# LinTempCont_4ch_V1_1.net
KiCad netlist of a schematic drawn in EAGLE
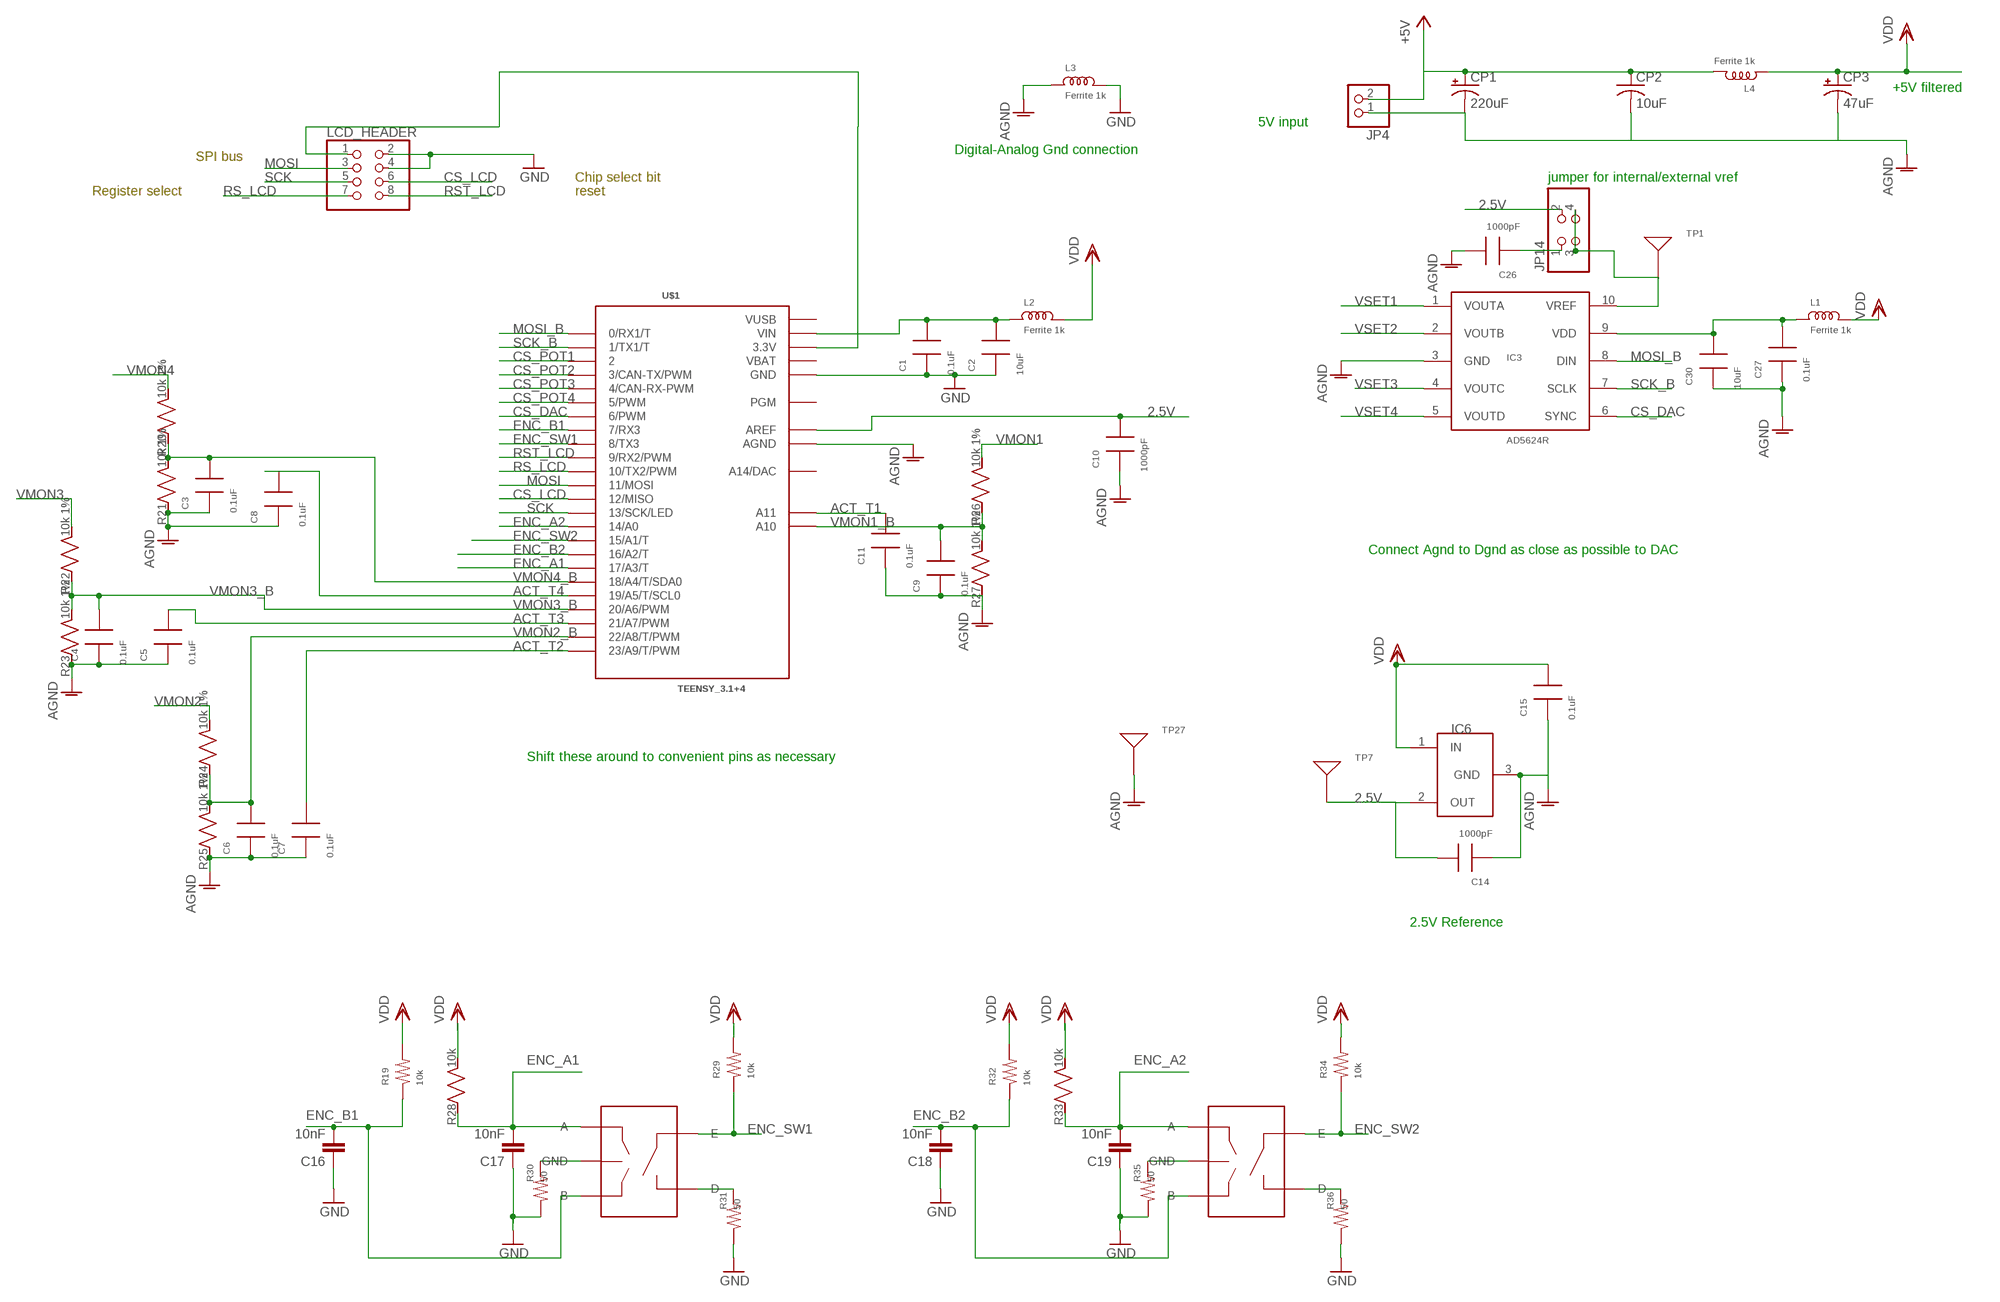
[diagram p0: schematic, sheet 1]
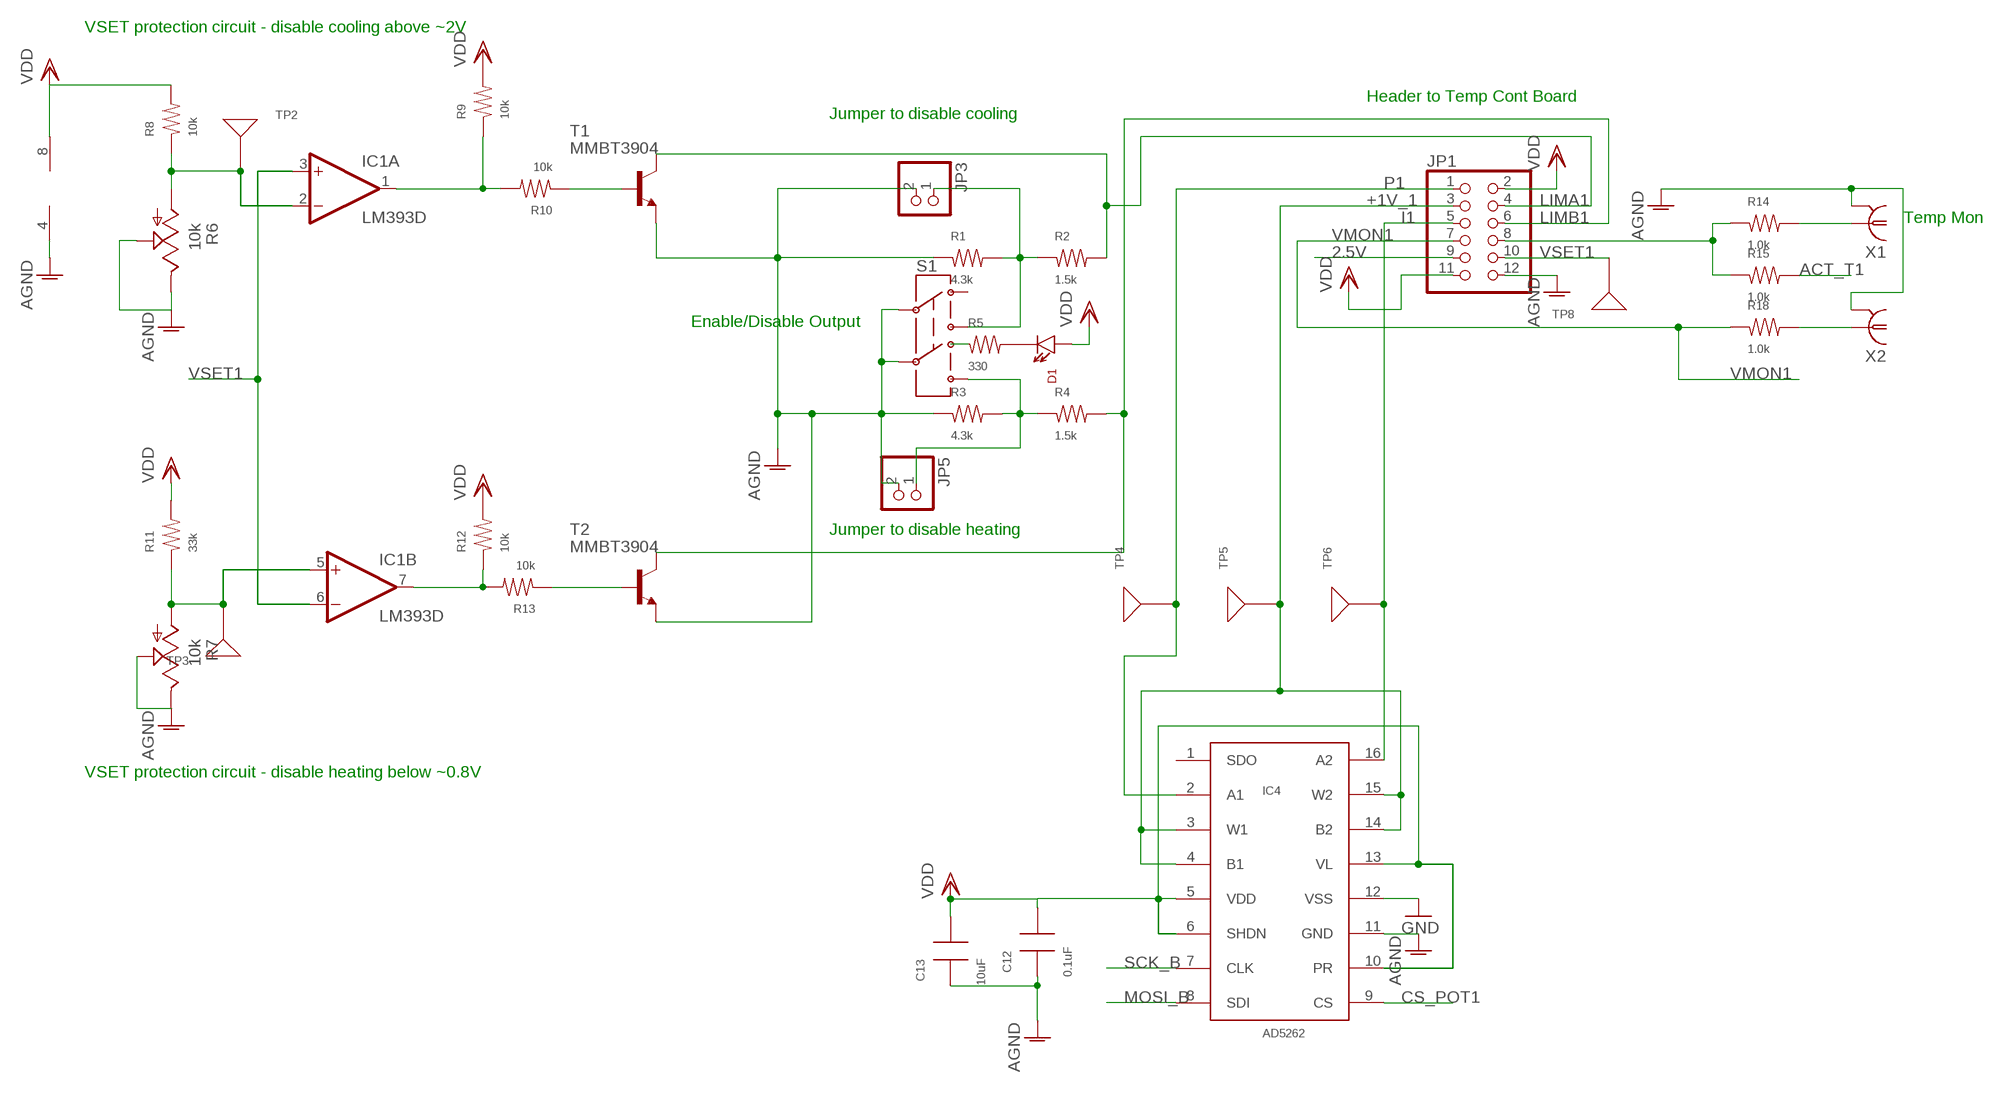
[diagram p1: schematic, sheet 2]
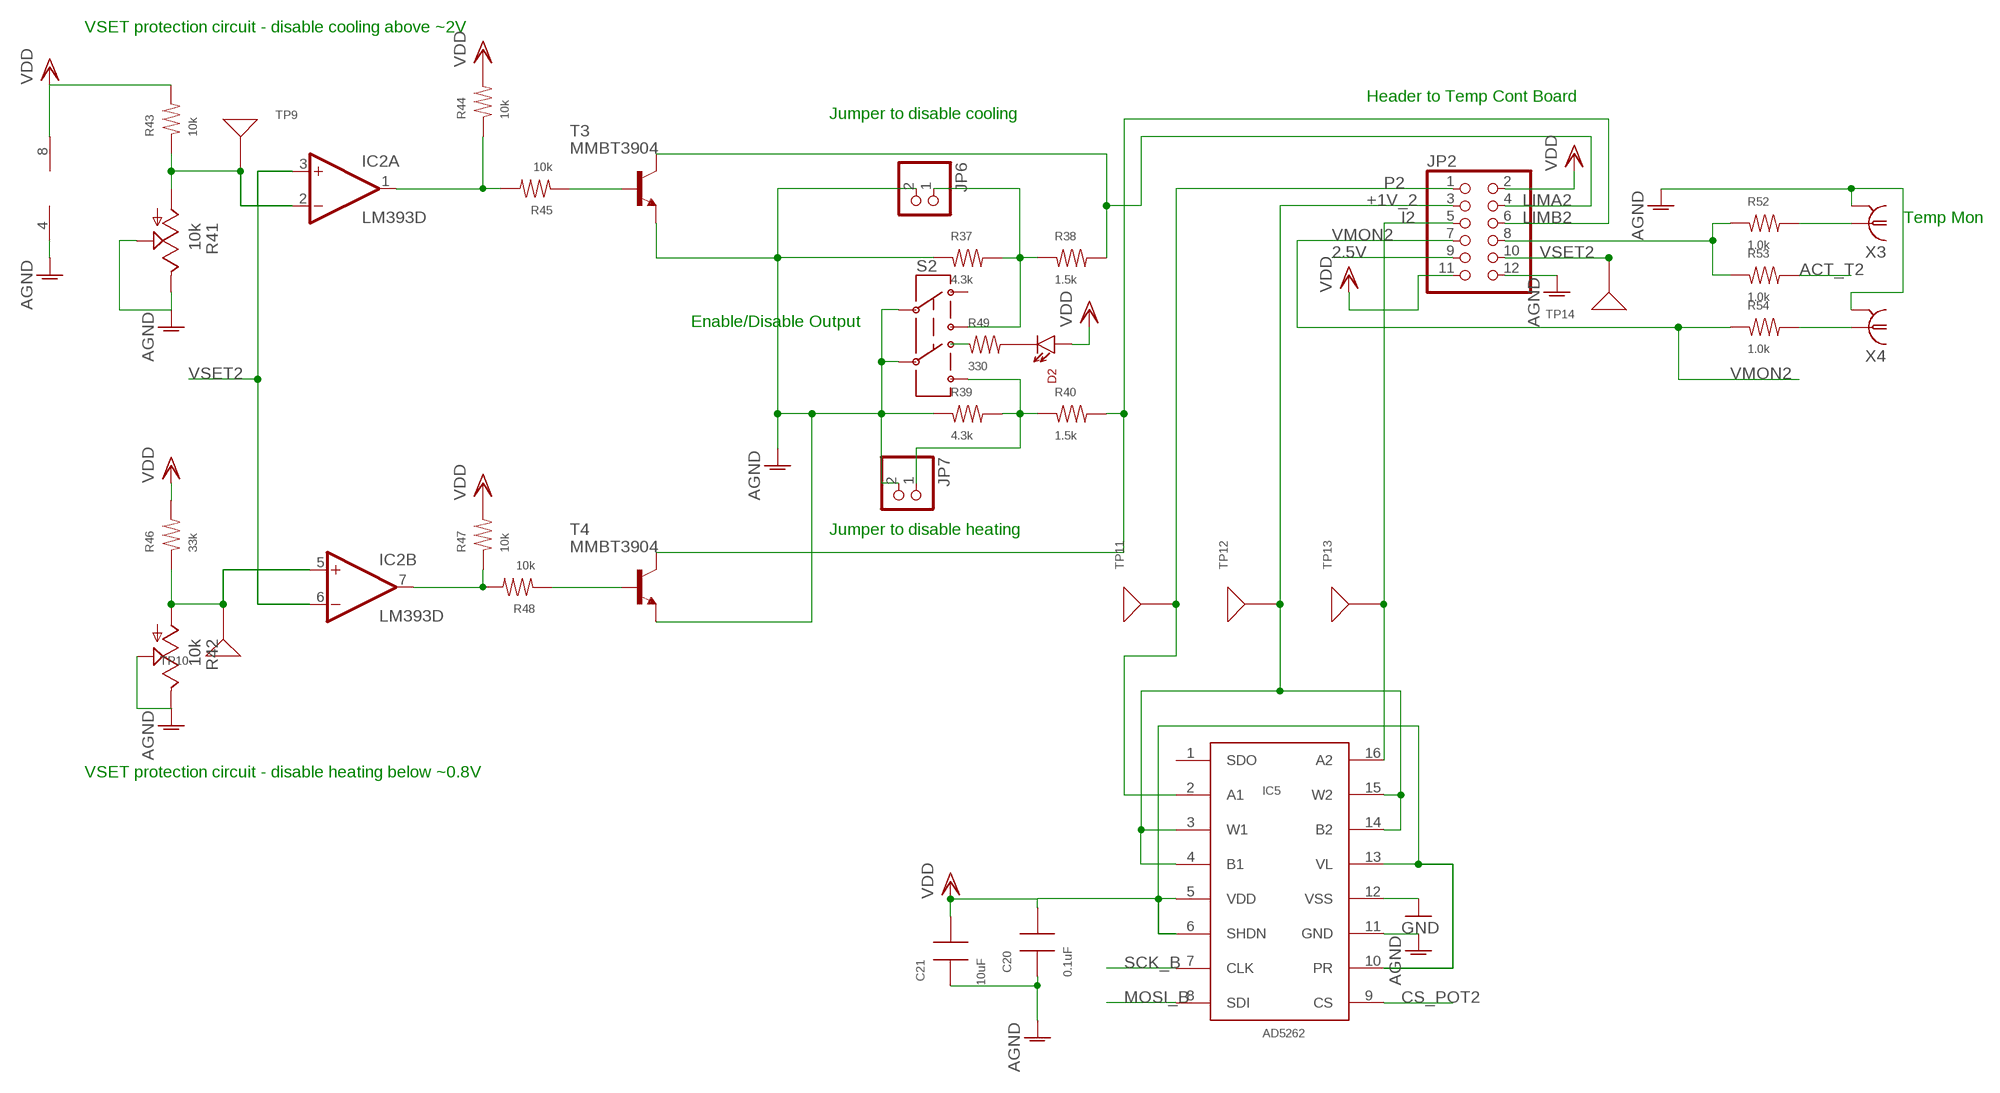
[diagram p2: schematic, sheet 3]
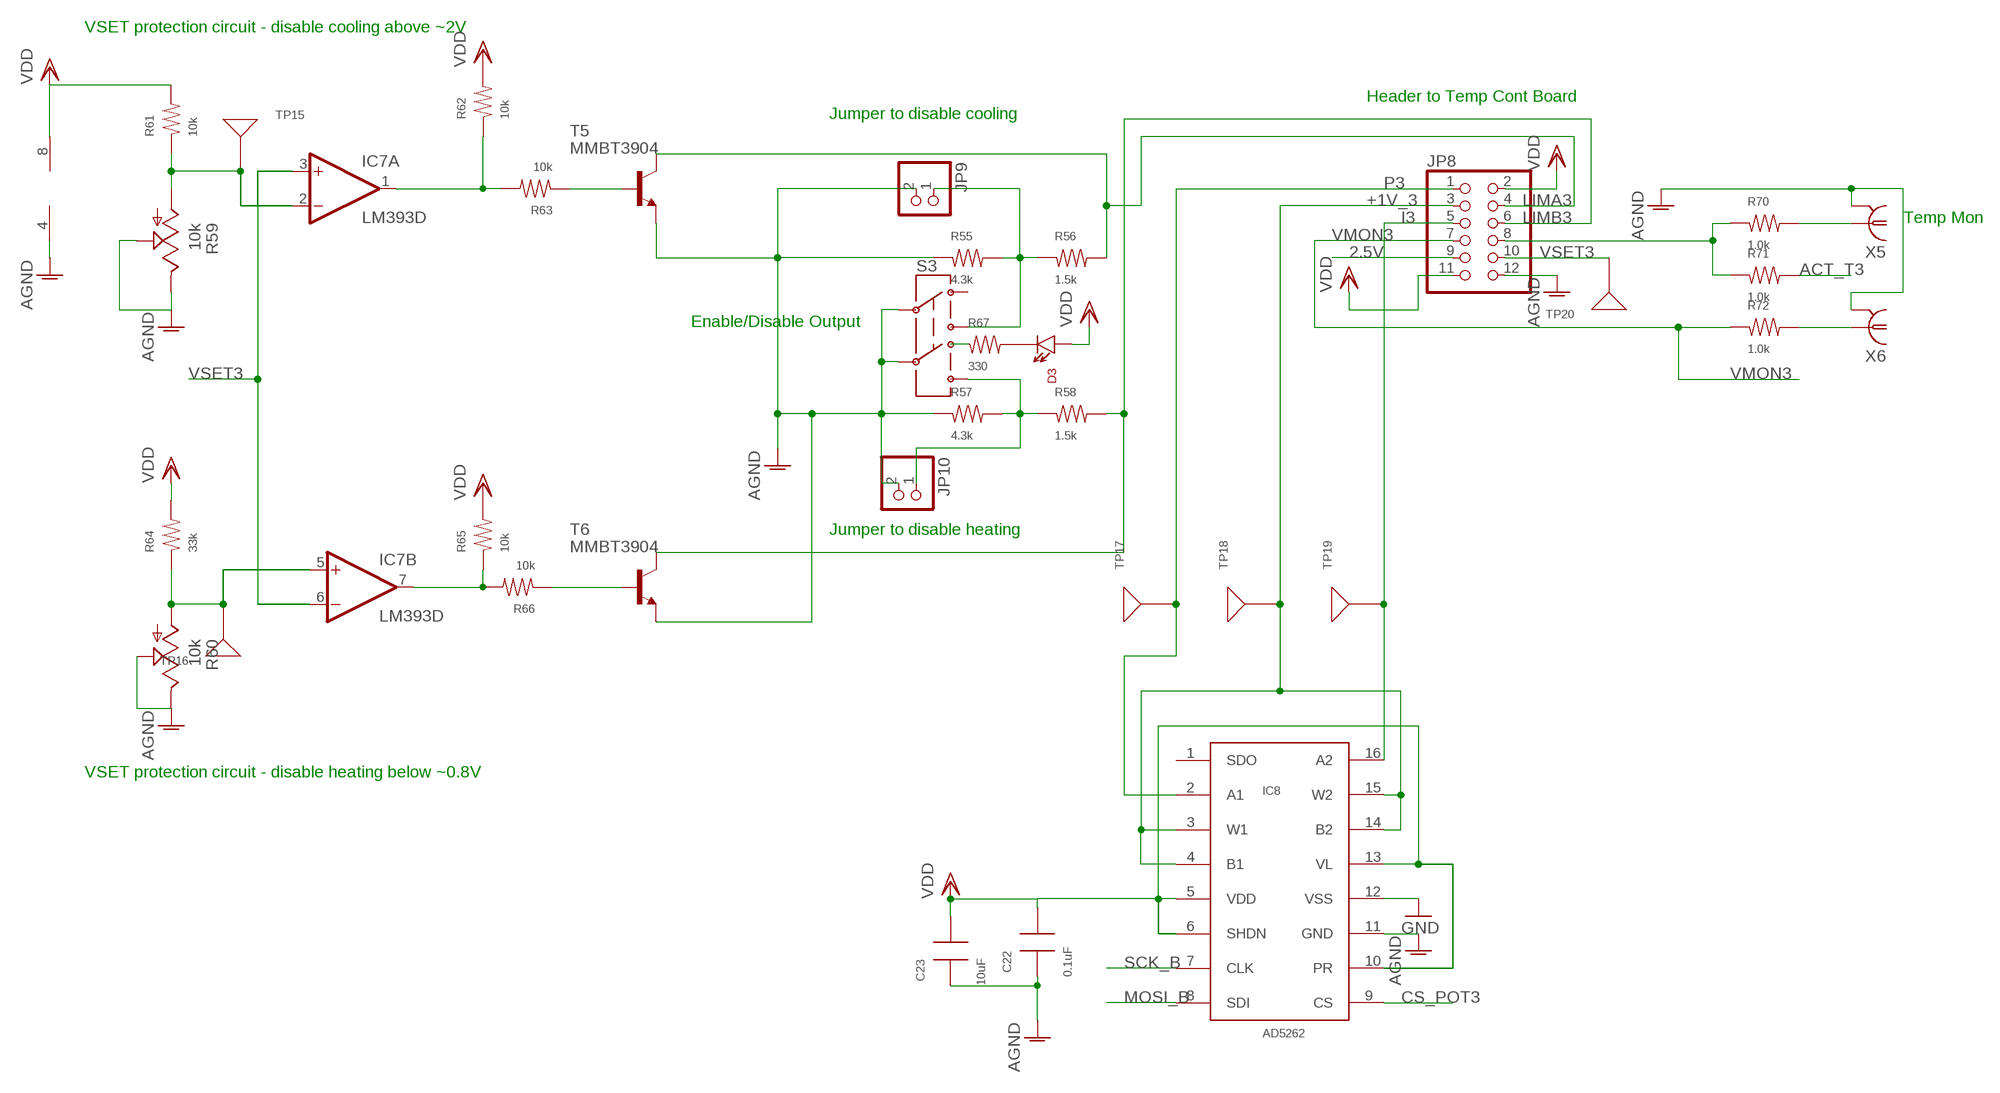
[diagram p3: schematic, sheet 4]
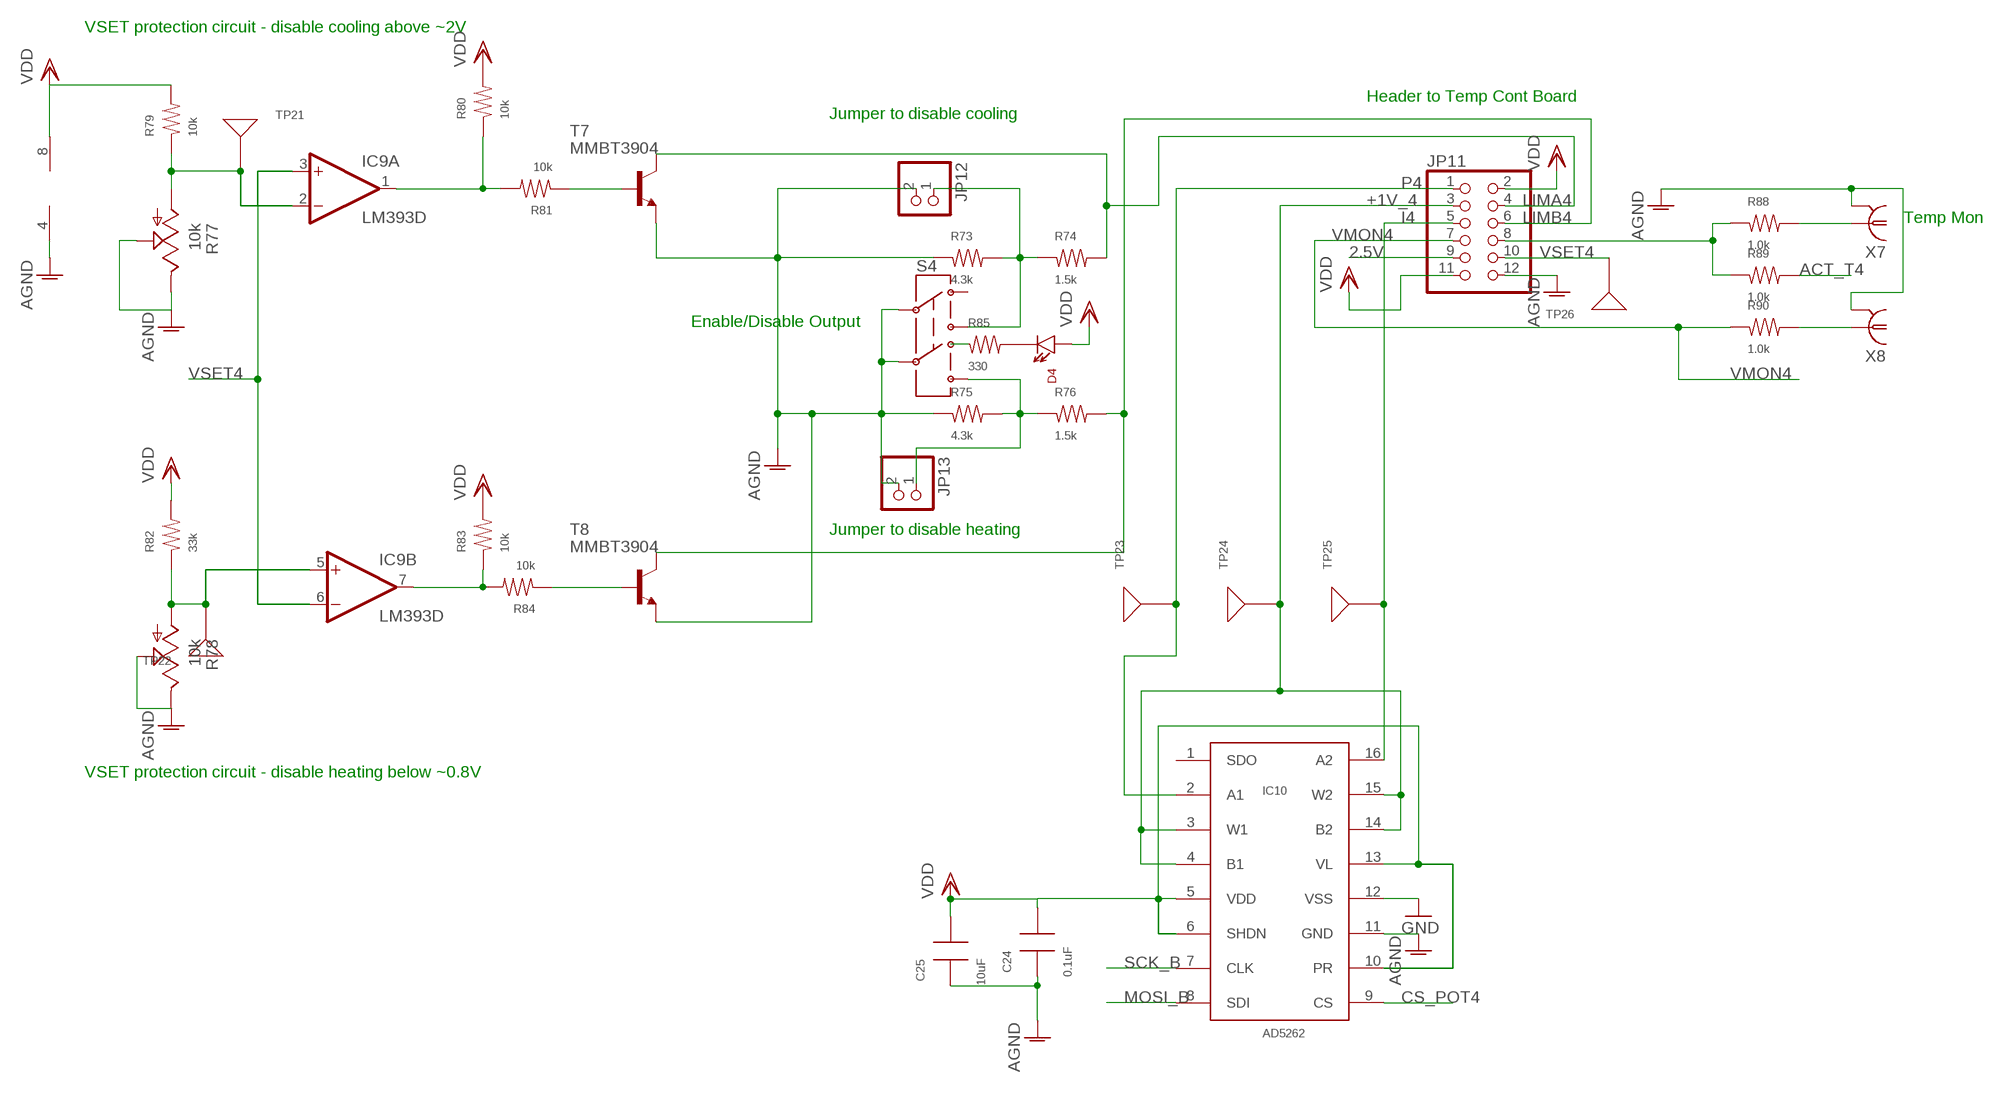
[diagram p4: schematic, sheet 5]

(export (version "E")
  (design (tool "Eeschema 10.0.6"))
  (components
    (comp (ref "C12")
      (value "0.1uF")
      (footprint "eagle-import:0603")
      (libsource (lib "eagle-import") (part "CAP0603"))
    )
    (comp (ref "C13")
      (value "10uF")
      (footprint "eagle-import:0805")
      (libsource (lib "eagle-import") (part "CAP0805"))
    )
    (comp (ref "D1")
      (value "LED/MINI-IND")
      (footprint "eagle-import:HLMP--F0010")
      (libsource (lib "eagle-import") (part "LED/MINI-IND"))
    )
    (comp (ref "IC1")
      (value "LM393D")
      (footprint "eagle-import:SO08")
      (libsource (lib "eagle-import") (part "LM393D"))
    )
    (comp (ref "IC4")
      (value "AD5262")
      (footprint "eagle-import:TSSOP16")
      (libsource (lib "eagle-import") (part "AD5262"))
    )
    (comp (ref "JP1")
      (value "PINHD-2X6/90")
      (footprint "eagle-import:2X06_90")
      (libsource (lib "eagle-import") (part "PINHD-2X6/90"))
    )
    (comp (ref "JP3")
      (value "PINHD-1X2")
      (footprint "eagle-import:1X02")
      (libsource (lib "eagle-import") (part "PINHD-1X2"))
    )
    (comp (ref "JP5")
      (value "PINHD-1X2")
      (footprint "eagle-import:1X02")
      (libsource (lib "eagle-import") (part "PINHD-1X2"))
    )
    (comp (ref "R1")
      (value "4.3k")
      (footprint "eagle-import:0603")
      (libsource (lib "eagle-import") (part "RES0603"))
    )
    (comp (ref "R2")
      (value "1.5k")
      (footprint "eagle-import:0603")
      (libsource (lib "eagle-import") (part "RES0603"))
    )
    (comp (ref "R3")
      (value "4.3k")
      (footprint "eagle-import:0603")
      (libsource (lib "eagle-import") (part "RES0603"))
    )
    (comp (ref "R4")
      (value "1.5k")
      (footprint "eagle-import:0603")
      (libsource (lib "eagle-import") (part "RES0603"))
    )
    (comp (ref "R5")
      (value "330")
      (footprint "eagle-import:0603")
      (libsource (lib "eagle-import") (part "RES0603"))
    )
    (comp (ref "R6")
      (value "10k")
      (footprint "eagle-import:64WPOT")
      (libsource (lib "eagle-import") (part "MODEL64_TRIMPOT/TOP-ADJ"))
    )
    (comp (ref "R7")
      (value "10k")
      (footprint "eagle-import:64WPOT")
      (libsource (lib "eagle-import") (part "MODEL64_TRIMPOT/TOP-ADJ"))
    )
    (comp (ref "R8")
      (value "10k")
      (footprint "eagle-import:0603")
      (libsource (lib "eagle-import") (part "RES0603"))
    )
    (comp (ref "R9")
      (value "10k")
      (footprint "eagle-import:0603")
      (libsource (lib "eagle-import") (part "RES0603"))
    )
    (comp (ref "R10")
      (value "10k")
      (footprint "eagle-import:0603")
      (libsource (lib "eagle-import") (part "RES0603"))
    )
    (comp (ref "R11")
      (value "33k")
      (footprint "eagle-import:0603")
      (libsource (lib "eagle-import") (part "RES0603"))
    )
    (comp (ref "R12")
      (value "10k")
      (footprint "eagle-import:0603")
      (libsource (lib "eagle-import") (part "RES0603"))
    )
    (comp (ref "R13")
      (value "10k")
      (footprint "eagle-import:0603")
      (libsource (lib "eagle-import") (part "RES0603"))
    )
    (comp (ref "R14")
      (value "1.0k")
      (footprint "eagle-import:0603")
      (libsource (lib "eagle-import") (part "RES0603"))
    )
    (comp (ref "R15")
      (value "1.0k")
      (footprint "eagle-import:0603")
      (libsource (lib "eagle-import") (part "RES0603"))
    )
    (comp (ref "R18")
      (value "1.0k")
      (footprint "eagle-import:0603")
      (libsource (lib "eagle-import") (part "RES0603"))
    )
    (comp (ref "S1")
      (value "SWITCH-DPDT/VER")
      (footprint "eagle-import:E-SWITCH-100-M7")
      (libsource (lib "eagle-import") (part "SWITCH-DPDT/VER"))
    )
    (comp (ref "T1")
      (value "MMBT3904")
      (footprint "eagle-import:SOT-23")
      (libsource (lib "eagle-import") (part "MMBT3904"))
    )
    (comp (ref "T2")
      (value "MMBT3904")
      (footprint "eagle-import:SOT-23")
      (libsource (lib "eagle-import") (part "MMBT3904"))
    )
    (comp (ref "TP2")
      (value "TESTPT")
      (footprint "eagle-import:1206TESTPAD")
      (libsource (lib "eagle-import") (part "TESTPT"))
    )
    (comp (ref "TP3")
      (value "TESTPT")
      (footprint "eagle-import:1206TESTPAD")
      (libsource (lib "eagle-import") (part "TESTPT"))
    )
    (comp (ref "TP4")
      (value "TESTPT")
      (footprint "eagle-import:1206TESTPAD")
      (libsource (lib "eagle-import") (part "TESTPT"))
    )
    (comp (ref "TP5")
      (value "TESTPT")
      (footprint "eagle-import:1206TESTPAD")
      (libsource (lib "eagle-import") (part "TESTPT"))
    )
    (comp (ref "TP6")
      (value "TESTPT")
      (footprint "eagle-import:1206TESTPAD")
      (libsource (lib "eagle-import") (part "TESTPT"))
    )
    (comp (ref "TP8")
      (value "TESTPT")
      (footprint "eagle-import:1206TESTPAD")
      (libsource (lib "eagle-import") (part "TESTPT"))
    )
    (comp (ref "X1")
      (value "BNC-H")
      (footprint "eagle-import:BNC90")
      (libsource (lib "eagle-import") (part "BNC-H"))
    )
    (comp (ref "X2")
      (value "BNC-H")
      (footprint "eagle-import:BNC90")
      (libsource (lib "eagle-import") (part "BNC-H"))
    )
    (comp (ref "C1")
      (value "0.1uF")
      (footprint "eagle-import:0603")
      (libsource (lib "eagle-import") (part "CAP0603"))
    )
    (comp (ref "C2")
      (value "10uF")
      (footprint "eagle-import:0805")
      (libsource (lib "eagle-import") (part "CAP0805"))
    )
    (comp (ref "C3")
      (value "0.1uF")
      (footprint "eagle-import:0603")
      (libsource (lib "eagle-import") (part "CAP0603"))
    )
    (comp (ref "C4")
      (value "0.1uF")
      (footprint "eagle-import:0603")
      (libsource (lib "eagle-import") (part "CAP0603"))
    )
    (comp (ref "C5")
      (value "0.1uF")
      (footprint "eagle-import:0603")
      (libsource (lib "eagle-import") (part "CAP0603"))
    )
    (comp (ref "C6")
      (value "0.1uF")
      (footprint "eagle-import:0603")
      (libsource (lib "eagle-import") (part "CAP0603"))
    )
    (comp (ref "C7")
      (value "0.1uF")
      (footprint "eagle-import:0603")
      (libsource (lib "eagle-import") (part "CAP0603"))
    )
    (comp (ref "C8")
      (value "0.1uF")
      (footprint "eagle-import:0603")
      (libsource (lib "eagle-import") (part "CAP0603"))
    )
    (comp (ref "C9")
      (value "0.1uF")
      (footprint "eagle-import:0603")
      (libsource (lib "eagle-import") (part "CAP0603"))
    )
    (comp (ref "C10")
      (value "1000pF")
      (footprint "eagle-import:0603")
      (libsource (lib "eagle-import") (part "CAP0603"))
    )
    (comp (ref "C11")
      (value "0.1uF")
      (footprint "eagle-import:0603")
      (libsource (lib "eagle-import") (part "CAP0603"))
    )
    (comp (ref "C14")
      (value "1000pF")
      (footprint "eagle-import:0603")
      (libsource (lib "eagle-import") (part "CAP0603"))
    )
    (comp (ref "C15")
      (value "0.1uF")
      (footprint "eagle-import:0603")
      (libsource (lib "eagle-import") (part "CAP0603"))
    )
    (comp (ref "C16")
      (value "10nF")
      (footprint "eagle-import:C0603")
      (libsource (lib "eagle-import") (part "C-EUC0603"))
    )
    (comp (ref "C17")
      (value "10nF")
      (footprint "eagle-import:C0603")
      (libsource (lib "eagle-import") (part "C-EUC0603"))
    )
    (comp (ref "C18")
      (value "10nF")
      (footprint "eagle-import:C0603")
      (libsource (lib "eagle-import") (part "C-EUC0603"))
    )
    (comp (ref "C19")
      (value "10nF")
      (footprint "eagle-import:C0603")
      (libsource (lib "eagle-import") (part "C-EUC0603"))
    )
    (comp (ref "C26")
      (value "1000pF")
      (footprint "eagle-import:0603")
      (libsource (lib "eagle-import") (part "CAP0603"))
    )
    (comp (ref "C27")
      (value "0.1uF")
      (footprint "eagle-import:0603")
      (libsource (lib "eagle-import") (part "CAP0603"))
    )
    (comp (ref "C30")
      (value "10uF")
      (footprint "eagle-import:0805")
      (libsource (lib "eagle-import") (part "CAP0805"))
    )
    (comp (ref "CP1")
      (value "220uF")
      (footprint "eagle-import:PANASONIC_F")
      (libsource (lib "eagle-import") (part "CPOL-USF"))
    )
    (comp (ref "CP2")
      (value "10uF")
      (footprint "eagle-import:C0805K")
      (libsource (lib "eagle-import") (part "C-USC0805K"))
    )
    (comp (ref "CP3")
      (value "47uF")
      (footprint "eagle-import:CT7343")
      (libsource (lib "eagle-import") (part "CPOL-USCT7343"))
    )
    (comp (ref "ENC1")
      (value "PEC09")
      (footprint "eagle-import:PEC092320FS")
      (libsource (lib "eagle-import") (part "PEC09"))
    )
    (comp (ref "ENC2")
      (value "PEC09")
      (footprint "eagle-import:PEC092320FS")
      (libsource (lib "eagle-import") (part "PEC09"))
    )
    (comp (ref "IC3")
      (value "AD5624R")
      (footprint "eagle-import:MSOP10")
      (libsource (lib "eagle-import") (part "AD5624R"))
    )
    (comp (ref "IC6")
      (value "TS6001")
      (footprint "eagle-import:SOT-23")
      (libsource (lib "eagle-import") (part "TS6001"))
    )
    (comp (ref "JP4")
      (value "SCRWTRM-1X2")
      (footprint "eagle-import:1X02_SCRWTRM")
      (libsource (lib "eagle-import") (part "SCRWTRM-1X2"))
    )
    (comp (ref "JP14")
      (value "PINHD-2X2")
      (footprint "eagle-import:2X02")
      (libsource (lib "eagle-import") (part "PINHD-2X2"))
    )
    (comp (ref "L1")
      (value "Ferrite 1k")
      (footprint "eagle-import:0805")
      (libsource (lib "eagle-import") (part "INDUCTOR-0805"))
    )
    (comp (ref "L2")
      (value "Ferrite 1k")
      (footprint "eagle-import:0805")
      (libsource (lib "eagle-import") (part "INDUCTOR-0805"))
    )
    (comp (ref "L3")
      (value "Ferrite 1k")
      (footprint "eagle-import:0805")
      (libsource (lib "eagle-import") (part "INDUCTOR-0805"))
    )
    (comp (ref "L4")
      (value "Ferrite 1k")
      (footprint "eagle-import:0805")
      (libsource (lib "eagle-import") (part "INDUCTOR-0805"))
    )
    (comp (ref "LCD_HEADER")
      (value "PINHD-2X4-SHROUD")
      (footprint "eagle-import:ML08")
      (libsource (lib "eagle-import") (part "PINHD-2X4-SHROUD"))
    )
    (comp (ref "R19")
      (value "10k")
      (footprint "eagle-import:0603")
      (libsource (lib "eagle-import") (part "RES0603"))
    )
    (comp (ref "R20")
      (value "10k 1%")
      (footprint "eagle-import:R_0603")
      (libsource (lib "eagle-import") (part "R_SMDR0603"))
    )
    (comp (ref "R21")
      (value "10k 1%")
      (footprint "eagle-import:R_0603")
      (libsource (lib "eagle-import") (part "R_SMDR0603"))
    )
    (comp (ref "R22")
      (value "10k 1%")
      (footprint "eagle-import:R_0603")
      (libsource (lib "eagle-import") (part "R_SMDR0603"))
    )
    (comp (ref "R23")
      (value "10k 1%")
      (footprint "eagle-import:R_0603")
      (libsource (lib "eagle-import") (part "R_SMDR0603"))
    )
    (comp (ref "R24")
      (value "10k 1%")
      (footprint "eagle-import:R_0603")
      (libsource (lib "eagle-import") (part "R_SMDR0603"))
    )
    (comp (ref "R25")
      (value "10k 1%")
      (footprint "eagle-import:R_0603")
      (libsource (lib "eagle-import") (part "R_SMDR0603"))
    )
    (comp (ref "R26")
      (value "10k 1%")
      (footprint "eagle-import:R_0603")
      (libsource (lib "eagle-import") (part "R_SMDR0603"))
    )
    (comp (ref "R27")
      (value "10k 1%")
      (footprint "eagle-import:R_0603")
      (libsource (lib "eagle-import") (part "R_SMDR0603"))
    )
    (comp (ref "R28")
      (value "10k")
      (footprint "eagle-import:R_0603")
      (libsource (lib "eagle-import") (part "R_SMDR0603"))
    )
    (comp (ref "R29")
      (value "10k")
      (footprint "eagle-import:0603")
      (libsource (lib "eagle-import") (part "RES0603"))
    )
    (comp (ref "R30")
      (value "50")
      (footprint "eagle-import:0603")
      (libsource (lib "eagle-import") (part "RES0603"))
    )
    (comp (ref "R31")
      (value "50")
      (footprint "eagle-import:0603")
      (libsource (lib "eagle-import") (part "RES0603"))
    )
    (comp (ref "R32")
      (value "10k")
      (footprint "eagle-import:0603")
      (libsource (lib "eagle-import") (part "RES0603"))
    )
    (comp (ref "R33")
      (value "10k")
      (footprint "eagle-import:R_0603")
      (libsource (lib "eagle-import") (part "R_SMDR0603"))
    )
    (comp (ref "R34")
      (value "10k")
      (footprint "eagle-import:0603")
      (libsource (lib "eagle-import") (part "RES0603"))
    )
    (comp (ref "R35")
      (value "50")
      (footprint "eagle-import:0603")
      (libsource (lib "eagle-import") (part "RES0603"))
    )
    (comp (ref "R36")
      (value "50")
      (footprint "eagle-import:0603")
      (libsource (lib "eagle-import") (part "RES0603"))
    )
    (comp (ref "TP1")
      (value "TESTPT")
      (footprint "eagle-import:1206TESTPAD")
      (libsource (lib "eagle-import") (part "TESTPT"))
    )
    (comp (ref "TP7")
      (value "TESTPT")
      (footprint "eagle-import:1206TESTPAD")
      (libsource (lib "eagle-import") (part "TESTPT"))
    )
    (comp (ref "TP27")
      (value "TESTPT")
      (footprint "eagle-import:1206TESTPAD")
      (libsource (lib "eagle-import") (part "TESTPT"))
    )
    (comp (ref "U$1")
      (value "TEENSY_3.1+4")
      (footprint "eagle-import:TEENSY_3.1+4")
      (libsource (lib "eagle-import") (part "TEENSY_3.1+4"))
    )
    (comp (ref "C20")
      (value "0.1uF")
      (footprint "eagle-import:0603")
      (libsource (lib "eagle-import") (part "CAP0603"))
    )
    (comp (ref "C21")
      (value "10uF")
      (footprint "eagle-import:0805")
      (libsource (lib "eagle-import") (part "CAP0805"))
    )
    (comp (ref "D2")
      (value "LED/MINI-IND")
      (footprint "eagle-import:HLMP--F0010")
      (libsource (lib "eagle-import") (part "LED/MINI-IND"))
    )
    (comp (ref "IC2")
      (value "LM393D")
      (footprint "eagle-import:SO08")
      (libsource (lib "eagle-import") (part "LM393D"))
    )
    (comp (ref "IC5")
      (value "AD5262")
      (footprint "eagle-import:TSSOP16")
      (libsource (lib "eagle-import") (part "AD5262"))
    )
    (comp (ref "JP2")
      (value "PINHD-2X6/90")
      (footprint "eagle-import:2X06_90")
      (libsource (lib "eagle-import") (part "PINHD-2X6/90"))
    )
    (comp (ref "JP6")
      (value "PINHD-1X2")
      (footprint "eagle-import:1X02")
      (libsource (lib "eagle-import") (part "PINHD-1X2"))
    )
    (comp (ref "JP7")
      (value "PINHD-1X2")
      (footprint "eagle-import:1X02")
      (libsource (lib "eagle-import") (part "PINHD-1X2"))
    )
    (comp (ref "R37")
      (value "4.3k")
      (footprint "eagle-import:0603")
      (libsource (lib "eagle-import") (part "RES0603"))
    )
    (comp (ref "R38")
      (value "1.5k")
      (footprint "eagle-import:0603")
      (libsource (lib "eagle-import") (part "RES0603"))
    )
    (comp (ref "R39")
      (value "4.3k")
      (footprint "eagle-import:0603")
      (libsource (lib "eagle-import") (part "RES0603"))
    )
    (comp (ref "R40")
      (value "1.5k")
      (footprint "eagle-import:0603")
      (libsource (lib "eagle-import") (part "RES0603"))
    )
    (comp (ref "R41")
      (value "10k")
      (footprint "eagle-import:64WPOT")
      (libsource (lib "eagle-import") (part "MODEL64_TRIMPOT/TOP-ADJ"))
    )
    (comp (ref "R42")
      (value "10k")
      (footprint "eagle-import:64WPOT")
      (libsource (lib "eagle-import") (part "MODEL64_TRIMPOT/TOP-ADJ"))
    )
    (comp (ref "R43")
      (value "10k")
      (footprint "eagle-import:0603")
      (libsource (lib "eagle-import") (part "RES0603"))
    )
    (comp (ref "R44")
      (value "10k")
      (footprint "eagle-import:0603")
      (libsource (lib "eagle-import") (part "RES0603"))
    )
    (comp (ref "R45")
      (value "10k")
      (footprint "eagle-import:0603")
      (libsource (lib "eagle-import") (part "RES0603"))
    )
    (comp (ref "R46")
      (value "33k")
      (footprint "eagle-import:0603")
      (libsource (lib "eagle-import") (part "RES0603"))
    )
    (comp (ref "R47")
      (value "10k")
      (footprint "eagle-import:0603")
      (libsource (lib "eagle-import") (part "RES0603"))
    )
    (comp (ref "R48")
      (value "10k")
      (footprint "eagle-import:0603")
      (libsource (lib "eagle-import") (part "RES0603"))
    )
    (comp (ref "R49")
      (value "330")
      (footprint "eagle-import:0603")
      (libsource (lib "eagle-import") (part "RES0603"))
    )
    (comp (ref "R52")
      (value "1.0k")
      (footprint "eagle-import:0603")
      (libsource (lib "eagle-import") (part "RES0603"))
    )
    (comp (ref "R53")
      (value "1.0k")
      (footprint "eagle-import:0603")
      (libsource (lib "eagle-import") (part "RES0603"))
    )
    (comp (ref "R54")
      (value "1.0k")
      (footprint "eagle-import:0603")
      (libsource (lib "eagle-import") (part "RES0603"))
    )
    (comp (ref "S2")
      (value "SWITCH-DPDT/VER")
      (footprint "eagle-import:E-SWITCH-100-M7")
      (libsource (lib "eagle-import") (part "SWITCH-DPDT/VER"))
    )
    (comp (ref "T3")
      (value "MMBT3904")
      (footprint "eagle-import:SOT-23")
      (libsource (lib "eagle-import") (part "MMBT3904"))
    )
    (comp (ref "T4")
      (value "MMBT3904")
      (footprint "eagle-import:SOT-23")
      (libsource (lib "eagle-import") (part "MMBT3904"))
    )
    (comp (ref "TP9")
      (value "TESTPT")
      (footprint "eagle-import:1206TESTPAD")
      (libsource (lib "eagle-import") (part "TESTPT"))
    )
    (comp (ref "TP10")
      (value "TESTPT")
      (footprint "eagle-import:1206TESTPAD")
      (libsource (lib "eagle-import") (part "TESTPT"))
    )
    (comp (ref "TP11")
      (value "TESTPT")
      (footprint "eagle-import:1206TESTPAD")
      (libsource (lib "eagle-import") (part "TESTPT"))
    )
    (comp (ref "TP12")
      (value "TESTPT")
      (footprint "eagle-import:1206TESTPAD")
      (libsource (lib "eagle-import") (part "TESTPT"))
    )
    (comp (ref "TP13")
      (value "TESTPT")
      (footprint "eagle-import:1206TESTPAD")
      (libsource (lib "eagle-import") (part "TESTPT"))
    )
    (comp (ref "TP14")
      (value "TESTPT")
      (footprint "eagle-import:1206TESTPAD")
      (libsource (lib "eagle-import") (part "TESTPT"))
    )
    (comp (ref "X3")
      (value "BNC-H")
      (footprint "eagle-import:BNC90")
      (libsource (lib "eagle-import") (part "BNC-H"))
    )
    (comp (ref "X4")
      (value "BNC-H")
      (footprint "eagle-import:BNC90")
      (libsource (lib "eagle-import") (part "BNC-H"))
    )
    (comp (ref "C22")
      (value "0.1uF")
      (footprint "eagle-import:0603")
      (libsource (lib "eagle-import") (part "CAP0603"))
    )
    (comp (ref "C23")
      (value "10uF")
      (footprint "eagle-import:0805")
      (libsource (lib "eagle-import") (part "CAP0805"))
    )
    (comp (ref "D3")
      (value "LED/MINI-IND")
      (footprint "eagle-import:HLMP--F0010")
      (libsource (lib "eagle-import") (part "LED/MINI-IND"))
    )
    (comp (ref "IC7")
      (value "LM393D")
      (footprint "eagle-import:SO08")
      (libsource (lib "eagle-import") (part "LM393D"))
    )
    (comp (ref "IC8")
      (value "AD5262")
      (footprint "eagle-import:TSSOP16")
      (libsource (lib "eagle-import") (part "AD5262"))
    )
    (comp (ref "JP8")
      (value "PINHD-2X6/90")
      (footprint "eagle-import:2X06_90")
      (libsource (lib "eagle-import") (part "PINHD-2X6/90"))
    )
    (comp (ref "JP9")
      (value "PINHD-1X2")
      (footprint "eagle-import:1X02")
      (libsource (lib "eagle-import") (part "PINHD-1X2"))
    )
    (comp (ref "JP10")
      (value "PINHD-1X2")
      (footprint "eagle-import:1X02")
      (libsource (lib "eagle-import") (part "PINHD-1X2"))
    )
    (comp (ref "R55")
      (value "4.3k")
      (footprint "eagle-import:0603")
      (libsource (lib "eagle-import") (part "RES0603"))
    )
    (comp (ref "R56")
      (value "1.5k")
      (footprint "eagle-import:0603")
      (libsource (lib "eagle-import") (part "RES0603"))
    )
    (comp (ref "R57")
      (value "4.3k")
      (footprint "eagle-import:0603")
      (libsource (lib "eagle-import") (part "RES0603"))
    )
    (comp (ref "R58")
      (value "1.5k")
      (footprint "eagle-import:0603")
      (libsource (lib "eagle-import") (part "RES0603"))
    )
    (comp (ref "R59")
      (value "10k")
      (footprint "eagle-import:64WPOT")
      (libsource (lib "eagle-import") (part "MODEL64_TRIMPOT/TOP-ADJ"))
    )
    (comp (ref "R60")
      (value "10k")
      (footprint "eagle-import:64WPOT")
      (libsource (lib "eagle-import") (part "MODEL64_TRIMPOT/TOP-ADJ"))
    )
    (comp (ref "R61")
      (value "10k")
      (footprint "eagle-import:0603")
      (libsource (lib "eagle-import") (part "RES0603"))
    )
    (comp (ref "R62")
      (value "10k")
      (footprint "eagle-import:0603")
      (libsource (lib "eagle-import") (part "RES0603"))
    )
    (comp (ref "R63")
      (value "10k")
      (footprint "eagle-import:0603")
      (libsource (lib "eagle-import") (part "RES0603"))
    )
    (comp (ref "R64")
      (value "33k")
      (footprint "eagle-import:0603")
      (libsource (lib "eagle-import") (part "RES0603"))
    )
    (comp (ref "R65")
      (value "10k")
      (footprint "eagle-import:0603")
      (libsource (lib "eagle-import") (part "RES0603"))
    )
    (comp (ref "R66")
      (value "10k")
      (footprint "eagle-import:0603")
      (libsource (lib "eagle-import") (part "RES0603"))
    )
    (comp (ref "R67")
      (value "330")
      (footprint "eagle-import:0603")
      (libsource (lib "eagle-import") (part "RES0603"))
    )
    (comp (ref "R70")
      (value "1.0k")
      (footprint "eagle-import:0603")
      (libsource (lib "eagle-import") (part "RES0603"))
    )
    (comp (ref "R71")
      (value "1.0k")
      (footprint "eagle-import:0603")
      (libsource (lib "eagle-import") (part "RES0603"))
    )
    (comp (ref "R72")
      (value "1.0k")
      (footprint "eagle-import:0603")
      (libsource (lib "eagle-import") (part "RES0603"))
    )
    (comp (ref "S3")
      (value "SWITCH-DPDT/VER")
      (footprint "eagle-import:E-SWITCH-100-M7")
      (libsource (lib "eagle-import") (part "SWITCH-DPDT/VER"))
    )
    (comp (ref "T5")
      (value "MMBT3904")
      (footprint "eagle-import:SOT-23")
      (libsource (lib "eagle-import") (part "MMBT3904"))
    )
    (comp (ref "T6")
      (value "MMBT3904")
      (footprint "eagle-import:SOT-23")
      (libsource (lib "eagle-import") (part "MMBT3904"))
    )
    (comp (ref "TP15")
      (value "TESTPT")
      (footprint "eagle-import:1206TESTPAD")
      (libsource (lib "eagle-import") (part "TESTPT"))
    )
    (comp (ref "TP16")
      (value "TESTPT")
      (footprint "eagle-import:1206TESTPAD")
      (libsource (lib "eagle-import") (part "TESTPT"))
    )
    (comp (ref "TP17")
      (value "TESTPT")
      (footprint "eagle-import:1206TESTPAD")
      (libsource (lib "eagle-import") (part "TESTPT"))
    )
    (comp (ref "TP18")
      (value "TESTPT")
      (footprint "eagle-import:1206TESTPAD")
      (libsource (lib "eagle-import") (part "TESTPT"))
    )
    (comp (ref "TP19")
      (value "TESTPT")
      (footprint "eagle-import:1206TESTPAD")
      (libsource (lib "eagle-import") (part "TESTPT"))
    )
    (comp (ref "TP20")
      (value "TESTPT")
      (footprint "eagle-import:1206TESTPAD")
      (libsource (lib "eagle-import") (part "TESTPT"))
    )
    (comp (ref "X5")
      (value "BNC-H")
      (footprint "eagle-import:BNC90")
      (libsource (lib "eagle-import") (part "BNC-H"))
    )
    (comp (ref "X6")
      (value "BNC-H")
      (footprint "eagle-import:BNC90")
      (libsource (lib "eagle-import") (part "BNC-H"))
    )
    (comp (ref "C24")
      (value "0.1uF")
      (footprint "eagle-import:0603")
      (libsource (lib "eagle-import") (part "CAP0603"))
    )
    (comp (ref "C25")
      (value "10uF")
      (footprint "eagle-import:0805")
      (libsource (lib "eagle-import") (part "CAP0805"))
    )
    (comp (ref "D4")
      (value "LED/MINI-IND")
      (footprint "eagle-import:HLMP--F0010")
      (libsource (lib "eagle-import") (part "LED/MINI-IND"))
    )
    (comp (ref "IC9")
      (value "LM393D")
      (footprint "eagle-import:SO08")
      (libsource (lib "eagle-import") (part "LM393D"))
    )
    (comp (ref "IC10")
      (value "AD5262")
      (footprint "eagle-import:TSSOP16")
      (libsource (lib "eagle-import") (part "AD5262"))
    )
    (comp (ref "JP11")
      (value "PINHD-2X6/90")
      (footprint "eagle-import:2X06_90")
      (libsource (lib "eagle-import") (part "PINHD-2X6/90"))
    )
    (comp (ref "JP12")
      (value "PINHD-1X2")
      (footprint "eagle-import:1X02")
      (libsource (lib "eagle-import") (part "PINHD-1X2"))
    )
    (comp (ref "JP13")
      (value "PINHD-1X2")
      (footprint "eagle-import:1X02")
      (libsource (lib "eagle-import") (part "PINHD-1X2"))
    )
    (comp (ref "R73")
      (value "4.3k")
      (footprint "eagle-import:0603")
      (libsource (lib "eagle-import") (part "RES0603"))
    )
    (comp (ref "R74")
      (value "1.5k")
      (footprint "eagle-import:0603")
      (libsource (lib "eagle-import") (part "RES0603"))
    )
    (comp (ref "R75")
      (value "4.3k")
      (footprint "eagle-import:0603")
      (libsource (lib "eagle-import") (part "RES0603"))
    )
    (comp (ref "R76")
      (value "1.5k")
      (footprint "eagle-import:0603")
      (libsource (lib "eagle-import") (part "RES0603"))
    )
    (comp (ref "R77")
      (value "10k")
      (footprint "eagle-import:64WPOT")
      (libsource (lib "eagle-import") (part "MODEL64_TRIMPOT/TOP-ADJ"))
    )
    (comp (ref "R78")
      (value "10k")
      (footprint "eagle-import:64WPOT")
      (libsource (lib "eagle-import") (part "MODEL64_TRIMPOT/TOP-ADJ"))
    )
    (comp (ref "R79")
      (value "10k")
      (footprint "eagle-import:0603")
      (libsource (lib "eagle-import") (part "RES0603"))
    )
    (comp (ref "R80")
      (value "10k")
      (footprint "eagle-import:0603")
      (libsource (lib "eagle-import") (part "RES0603"))
    )
    (comp (ref "R81")
      (value "10k")
      (footprint "eagle-import:0603")
      (libsource (lib "eagle-import") (part "RES0603"))
    )
    (comp (ref "R82")
      (value "33k")
      (footprint "eagle-import:0603")
      (libsource (lib "eagle-import") (part "RES0603"))
    )
    (comp (ref "R83")
      (value "10k")
      (footprint "eagle-import:0603")
      (libsource (lib "eagle-import") (part "RES0603"))
    )
    (comp (ref "R84")
      (value "10k")
      (footprint "eagle-import:0603")
      (libsource (lib "eagle-import") (part "RES0603"))
    )
    (comp (ref "R85")
      (value "330")
      (footprint "eagle-import:0603")
      (libsource (lib "eagle-import") (part "RES0603"))
    )
    (comp (ref "R88")
      (value "1.0k")
      (footprint "eagle-import:0603")
      (libsource (lib "eagle-import") (part "RES0603"))
    )
    (comp (ref "R89")
      (value "1.0k")
      (footprint "eagle-import:0603")
      (libsource (lib "eagle-import") (part "RES0603"))
    )
    (comp (ref "R90")
      (value "1.0k")
      (footprint "eagle-import:0603")
      (libsource (lib "eagle-import") (part "RES0603"))
    )
    (comp (ref "S4")
      (value "SWITCH-DPDT/VER")
      (footprint "eagle-import:E-SWITCH-100-M7")
      (libsource (lib "eagle-import") (part "SWITCH-DPDT/VER"))
    )
    (comp (ref "T7")
      (value "MMBT3904")
      (footprint "eagle-import:SOT-23")
      (libsource (lib "eagle-import") (part "MMBT3904"))
    )
    (comp (ref "T8")
      (value "MMBT3904")
      (footprint "eagle-import:SOT-23")
      (libsource (lib "eagle-import") (part "MMBT3904"))
    )
    (comp (ref "TP21")
      (value "TESTPT")
      (footprint "eagle-import:1206TESTPAD")
      (libsource (lib "eagle-import") (part "TESTPT"))
    )
    (comp (ref "TP22")
      (value "TESTPT")
      (footprint "eagle-import:1206TESTPAD")
      (libsource (lib "eagle-import") (part "TESTPT"))
    )
    (comp (ref "TP23")
      (value "TESTPT")
      (footprint "eagle-import:1206TESTPAD")
      (libsource (lib "eagle-import") (part "TESTPT"))
    )
    (comp (ref "TP24")
      (value "TESTPT")
      (footprint "eagle-import:1206TESTPAD")
      (libsource (lib "eagle-import") (part "TESTPT"))
    )
    (comp (ref "TP25")
      (value "TESTPT")
      (footprint "eagle-import:1206TESTPAD")
      (libsource (lib "eagle-import") (part "TESTPT"))
    )
    (comp (ref "TP26")
      (value "TESTPT")
      (footprint "eagle-import:1206TESTPAD")
      (libsource (lib "eagle-import") (part "TESTPT"))
    )
    (comp (ref "X7")
      (value "BNC-H")
      (footprint "eagle-import:BNC90")
      (libsource (lib "eagle-import") (part "BNC-H"))
    )
    (comp (ref "X8")
      (value "BNC-H")
      (footprint "eagle-import:BNC90")
      (libsource (lib "eagle-import") (part "BNC-H"))
    )
  )
  (nets
    (net (code "1") (name "+1V_1") (class "Default")
      (node (ref "IC4") (pin "14") (pinfunction "B2_14") (pintype "bidirectional"))
      (node (ref "IC4") (pin "15") (pinfunction "W2_15") (pintype "bidirectional"))
      (node (ref "IC4") (pin "3") (pinfunction "W1_3") (pintype "bidirectional"))
      (node (ref "IC4") (pin "4") (pinfunction "B1_4") (pintype "bidirectional"))
      (node (ref "JP1") (pin "3") (pinfunction "3_3") (pintype "passive"))
      (node (ref "TP5") (pin "P$1") (pinfunction "P$1_P$1") (pintype "bidirectional"))
    )
    (net (code "2") (name "+1V_2") (class "Default")
      (node (ref "IC5") (pin "14") (pinfunction "B2_14") (pintype "bidirectional"))
      (node (ref "IC5") (pin "15") (pinfunction "W2_15") (pintype "bidirectional"))
      (node (ref "IC5") (pin "3") (pinfunction "W1_3") (pintype "bidirectional"))
      (node (ref "IC5") (pin "4") (pinfunction "B1_4") (pintype "bidirectional"))
      (node (ref "JP2") (pin "3") (pinfunction "3_3") (pintype "passive"))
      (node (ref "TP12") (pin "P$1") (pinfunction "P$1_P$1") (pintype "bidirectional"))
    )
    (net (code "3") (name "+1V_3") (class "Default")
      (node (ref "IC8") (pin "14") (pinfunction "B2_14") (pintype "bidirectional"))
      (node (ref "IC8") (pin "15") (pinfunction "W2_15") (pintype "bidirectional"))
      (node (ref "IC8") (pin "3") (pinfunction "W1_3") (pintype "bidirectional"))
      (node (ref "IC8") (pin "4") (pinfunction "B1_4") (pintype "bidirectional"))
      (node (ref "JP8") (pin "3") (pinfunction "3_3") (pintype "passive"))
      (node (ref "TP18") (pin "P$1") (pinfunction "P$1_P$1") (pintype "bidirectional"))
    )
    (net (code "4") (name "+1V_4") (class "Default")
      (node (ref "IC10") (pin "14") (pinfunction "B2_14") (pintype "bidirectional"))
      (node (ref "IC10") (pin "15") (pinfunction "W2_15") (pintype "bidirectional"))
      (node (ref "IC10") (pin "3") (pinfunction "W1_3") (pintype "bidirectional"))
      (node (ref "IC10") (pin "4") (pinfunction "B1_4") (pintype "bidirectional"))
      (node (ref "JP11") (pin "3") (pinfunction "3_3") (pintype "passive"))
      (node (ref "TP24") (pin "P$1") (pinfunction "P$1_P$1") (pintype "bidirectional"))
    )
    (net (code "5") (name "+5V") (class "Default")
      (node (ref "CP1") (pin "+") (pinfunction "+_+") (pintype "passive"))
      (node (ref "CP2") (pin "1") (pinfunction "1_1") (pintype "passive"))
      (node (ref "JP4") (pin "2") (pinfunction "2_2") (pintype "passive"))
      (node (ref "L4") (pin "2") (pinfunction "P$2_2") (pintype "passive"))
    )
    (net (code "6") (name "2.5V") (class "Default")
      (node (ref "C10") (pin "2") (pinfunction "P$2_2") (pintype "passive"))
      (node (ref "C14") (pin "2") (pinfunction "P$2_2") (pintype "passive"))
      (node (ref "IC6") (pin "2") (pinfunction "OUT_2") (pintype "bidirectional"))
      (node (ref "JP1") (pin "9") (pinfunction "9_9") (pintype "passive"))
      (node (ref "JP11") (pin "9") (pinfunction "9_9") (pintype "passive"))
      (node (ref "JP14") (pin "2") (pinfunction "2_2") (pintype "passive"))
      (node (ref "JP2") (pin "9") (pinfunction "9_9") (pintype "passive"))
      (node (ref "JP8") (pin "9") (pinfunction "9_9") (pintype "passive"))
      (node (ref "TP7") (pin "P$1") (pinfunction "P$1_P$1") (pintype "bidirectional"))
      (node (ref "U$1") (pin "AREF") (pinfunction "AREF_AREF") (pintype "power_in"))
    )
    (net (code "7") (name "ACT_T1") (class "Default")
      (node (ref "C11") (pin "2") (pinfunction "P$2_2") (pintype "passive"))
      (node (ref "R15") (pin "2") (pinfunction "P$2_2") (pintype "passive"))
      (node (ref "U$1") (pin "A11") (pinfunction "A11_A11") (pintype "bidirectional"))
    )
    (net (code "8") (name "ACT_T2") (class "Default")
      (node (ref "C7") (pin "2") (pinfunction "P$2_2") (pintype "passive"))
      (node (ref "R53") (pin "2") (pinfunction "P$2_2") (pintype "passive"))
      (node (ref "U$1") (pin "23/A9") (pinfunction "23/A9/T/PWM_23/A9") (pintype "bidirectional"))
    )
    (net (code "9") (name "ACT_T3") (class "Default")
      (node (ref "C5") (pin "2") (pinfunction "P$2_2") (pintype "passive"))
      (node (ref "R71") (pin "2") (pinfunction "P$2_2") (pintype "passive"))
      (node (ref "U$1") (pin "21/A7") (pinfunction "21/A7/PWM_21/A7") (pintype "bidirectional"))
    )
    (net (code "10") (name "ACT_T4") (class "Default")
      (node (ref "C8") (pin "2") (pinfunction "P$2_2") (pintype "passive"))
      (node (ref "R89") (pin "2") (pinfunction "P$2_2") (pintype "passive"))
      (node (ref "U$1") (pin "19/A5") (pinfunction "19/A5/T/SCL0_19/A5") (pintype "bidirectional"))
    )
    (net (code "11") (name "AGND") (class "Default")
      (node (ref "C10") (pin "1") (pinfunction "P$1_1") (pintype "passive"))
      (node (ref "C11") (pin "1") (pinfunction "P$1_1") (pintype "passive"))
      (node (ref "C12") (pin "1") (pinfunction "P$1_1") (pintype "passive"))
      (node (ref "C13") (pin "1") (pinfunction "P$1_1") (pintype "passive"))
      (node (ref "C14") (pin "1") (pinfunction "P$1_1") (pintype "passive"))
      (node (ref "C15") (pin "1") (pinfunction "P$1_1") (pintype "passive"))
      (node (ref "C20") (pin "1") (pinfunction "P$1_1") (pintype "passive"))
      (node (ref "C21") (pin "1") (pinfunction "P$1_1") (pintype "passive"))
      (node (ref "C22") (pin "1") (pinfunction "P$1_1") (pintype "passive"))
      (node (ref "C23") (pin "1") (pinfunction "P$1_1") (pintype "passive"))
      (node (ref "C24") (pin "1") (pinfunction "P$1_1") (pintype "passive"))
      (node (ref "C25") (pin "1") (pinfunction "P$1_1") (pintype "passive"))
      (node (ref "C26") (pin "2") (pinfunction "P$2_2") (pintype "passive"))
      (node (ref "C27") (pin "1") (pinfunction "P$1_1") (pintype "passive"))
      (node (ref "C3") (pin "1") (pinfunction "P$1_1") (pintype "passive"))
      (node (ref "C30") (pin "1") (pinfunction "P$1_1") (pintype "passive"))
      (node (ref "C4") (pin "1") (pinfunction "P$1_1") (pintype "passive"))
      (node (ref "C5") (pin "1") (pinfunction "P$1_1") (pintype "passive"))
      (node (ref "C6") (pin "1") (pinfunction "P$1_1") (pintype "passive"))
      (node (ref "C7") (pin "1") (pinfunction "P$1_1") (pintype "passive"))
      (node (ref "C8") (pin "1") (pinfunction "P$1_1") (pintype "passive"))
      (node (ref "C9") (pin "1") (pinfunction "P$1_1") (pintype "passive"))
      (node (ref "CP1") (pin "-") (pinfunction "-_-") (pintype "passive"))
      (node (ref "CP2") (pin "2") (pinfunction "2_2") (pintype "passive"))
      (node (ref "CP3") (pin "-") (pinfunction "-_-") (pintype "passive"))
      (node (ref "IC1") (pin "4") (pinfunction "V-_4") (pintype "power_in"))
      (node (ref "IC10") (pin "11") (pinfunction "GND_11") (pintype "power_in"))
      (node (ref "IC2") (pin "4") (pinfunction "V-_4") (pintype "power_in"))
      (node (ref "IC3") (pin "3") (pinfunction "GND_3") (pintype "power_in"))
      (node (ref "IC4") (pin "11") (pinfunction "GND_11") (pintype "power_in"))
      (node (ref "IC5") (pin "11") (pinfunction "GND_11") (pintype "power_in"))
      (node (ref "IC6") (pin "3") (pinfunction "GND_3") (pintype "bidirectional"))
      (node (ref "IC7") (pin "4") (pinfunction "V-_4") (pintype "power_in"))
      (node (ref "IC8") (pin "11") (pinfunction "GND_11") (pintype "power_in"))
      (node (ref "IC9") (pin "4") (pinfunction "V-_4") (pintype "power_in"))
      (node (ref "JP1") (pin "12") (pinfunction "12_12") (pintype "passive"))
      (node (ref "JP10") (pin "2") (pinfunction "2_2") (pintype "passive"))
      (node (ref "JP11") (pin "12") (pinfunction "12_12") (pintype "passive"))
      (node (ref "JP12") (pin "2") (pinfunction "2_2") (pintype "passive"))
      (node (ref "JP13") (pin "2") (pinfunction "2_2") (pintype "passive"))
      (node (ref "JP2") (pin "12") (pinfunction "12_12") (pintype "passive"))
      (node (ref "JP3") (pin "2") (pinfunction "2_2") (pintype "passive"))
      (node (ref "JP4") (pin "1") (pinfunction "1_1") (pintype "passive"))
      (node (ref "JP5") (pin "2") (pinfunction "2_2") (pintype "passive"))
      (node (ref "JP6") (pin "2") (pinfunction "2_2") (pintype "passive"))
      (node (ref "JP7") (pin "2") (pinfunction "2_2") (pintype "passive"))
      (node (ref "JP8") (pin "12") (pinfunction "12_12") (pintype "passive"))
      (node (ref "JP9") (pin "2") (pinfunction "2_2") (pintype "passive"))
      (node (ref "L3") (pin "1") (pinfunction "P$1_1") (pintype "passive"))
      (node (ref "R1") (pin "1") (pinfunction "P$1_1") (pintype "passive"))
      (node (ref "R21") (pin "P$1") (pinfunction "1_P$1") (pintype "passive"))
      (node (ref "R23") (pin "P$1") (pinfunction "1_P$1") (pintype "passive"))
      (node (ref "R25") (pin "P$1") (pinfunction "1_P$1") (pintype "passive"))
      (node (ref "R27") (pin "P$1") (pinfunction "1_P$1") (pintype "passive"))
      (node (ref "R3") (pin "1") (pinfunction "P$1_1") (pintype "passive"))
      (node (ref "R37") (pin "1") (pinfunction "P$1_1") (pintype "passive"))
      (node (ref "R39") (pin "1") (pinfunction "P$1_1") (pintype "passive"))
      (node (ref "R41") (pin "P$2") (pinfunction "2_P$2") (pintype "passive"))
      (node (ref "R41") (pin "P$3") (pinfunction "3_P$3") (pintype "passive"))
      (node (ref "R42") (pin "P$2") (pinfunction "2_P$2") (pintype "passive"))
      (node (ref "R42") (pin "P$3") (pinfunction "3_P$3") (pintype "passive"))
      (node (ref "R55") (pin "1") (pinfunction "P$1_1") (pintype "passive"))
      (node (ref "R57") (pin "1") (pinfunction "P$1_1") (pintype "passive"))
      (node (ref "R59") (pin "P$2") (pinfunction "2_P$2") (pintype "passive"))
      (node (ref "R59") (pin "P$3") (pinfunction "3_P$3") (pintype "passive"))
      (node (ref "R6") (pin "P$2") (pinfunction "2_P$2") (pintype "passive"))
      (node (ref "R6") (pin "P$3") (pinfunction "3_P$3") (pintype "passive"))
      (node (ref "R60") (pin "P$2") (pinfunction "2_P$2") (pintype "passive"))
      (node (ref "R60") (pin "P$3") (pinfunction "3_P$3") (pintype "passive"))
      (node (ref "R7") (pin "P$2") (pinfunction "2_P$2") (pintype "passive"))
      (node (ref "R7") (pin "P$3") (pinfunction "3_P$3") (pintype "passive"))
      (node (ref "R73") (pin "1") (pinfunction "P$1_1") (pintype "passive"))
      (node (ref "R75") (pin "1") (pinfunction "P$1_1") (pintype "passive"))
      (node (ref "R77") (pin "P$2") (pinfunction "2_P$2") (pintype "passive"))
      (node (ref "R77") (pin "P$3") (pinfunction "3_P$3") (pintype "passive"))
      (node (ref "R78") (pin "P$2") (pinfunction "2_P$2") (pintype "passive"))
      (node (ref "R78") (pin "P$3") (pinfunction "3_P$3") (pintype "passive"))
      (node (ref "S1") (pin "P$2") (pinfunction "2_P$2") (pintype "bidirectional"))
      (node (ref "S1") (pin "P$5") (pinfunction "5_P$5") (pintype "bidirectional"))
      (node (ref "S2") (pin "P$2") (pinfunction "2_P$2") (pintype "bidirectional"))
      (node (ref "S2") (pin "P$5") (pinfunction "5_P$5") (pintype "bidirectional"))
      (node (ref "S3") (pin "P$2") (pinfunction "2_P$2") (pintype "bidirectional"))
      (node (ref "S3") (pin "P$5") (pinfunction "5_P$5") (pintype "bidirectional"))
      (node (ref "S4") (pin "P$2") (pinfunction "2_P$2") (pintype "bidirectional"))
      (node (ref "S4") (pin "P$5") (pinfunction "5_P$5") (pintype "bidirectional"))
      (node (ref "T1") (pin "2") (pinfunction "E_2") (pintype "passive"))
      (node (ref "T2") (pin "2") (pinfunction "E_2") (pintype "passive"))
      (node (ref "T3") (pin "2") (pinfunction "E_2") (pintype "passive"))
      (node (ref "T4") (pin "2") (pinfunction "E_2") (pintype "passive"))
      (node (ref "T5") (pin "2") (pinfunction "E_2") (pintype "passive"))
      (node (ref "T6") (pin "2") (pinfunction "E_2") (pintype "passive"))
      (node (ref "T7") (pin "2") (pinfunction "E_2") (pintype "passive"))
      (node (ref "T8") (pin "2") (pinfunction "E_2") (pintype "passive"))
      (node (ref "TP27") (pin "P$1") (pinfunction "P$1_P$1") (pintype "bidirectional"))
      (node (ref "U$1") (pin "AGND") (pinfunction "AGND_AGND") (pintype "power_in"))
      (node (ref "X1") (pin "2") (pinfunction "2_2") (pintype "passive"))
      (node (ref "X2") (pin "2") (pinfunction "2_2") (pintype "passive"))
      (node (ref "X3") (pin "2") (pinfunction "2_2") (pintype "passive"))
      (node (ref "X4") (pin "2") (pinfunction "2_2") (pintype "passive"))
      (node (ref "X5") (pin "2") (pinfunction "2_2") (pintype "passive"))
      (node (ref "X6") (pin "2") (pinfunction "2_2") (pintype "passive"))
      (node (ref "X7") (pin "2") (pinfunction "2_2") (pintype "passive"))
      (node (ref "X8") (pin "2") (pinfunction "2_2") (pintype "passive"))
    )
    (net (code "12") (name "CS_DAC") (class "Default")
      (node (ref "IC3") (pin "6") (pinfunction "SYNC_6") (pintype "bidirectional"))
      (node (ref "U$1") (pin "6") (pinfunction "6/PWM_6") (pintype "bidirectional"))
    )
    (net (code "13") (name "CS_LCD") (class "Default")
      (node (ref "LCD_HEADER") (pin "6") (pinfunction "6_6") (pintype "passive"))
      (node (ref "U$1") (pin "12") (pinfunction "12/MISO_12") (pintype "bidirectional"))
    )
    (net (code "14") (name "CS_POT1") (class "Default")
      (node (ref "IC4") (pin "9") (pinfunction "CS_9") (pintype "bidirectional"))
      (node (ref "U$1") (pin "2") (pinfunction "2_2") (pintype "bidirectional"))
    )
    (net (code "15") (name "CS_POT2") (class "Default")
      (node (ref "IC5") (pin "9") (pinfunction "CS_9") (pintype "bidirectional"))
      (node (ref "U$1") (pin "3") (pinfunction "3/CAN-TX/PWM_3") (pintype "bidirectional"))
    )
    (net (code "16") (name "CS_POT3") (class "Default")
      (node (ref "IC8") (pin "9") (pinfunction "CS_9") (pintype "bidirectional"))
      (node (ref "U$1") (pin "4") (pinfunction "4/CAN-RX-PWM_4") (pintype "bidirectional"))
    )
    (net (code "17") (name "CS_POT4") (class "Default")
      (node (ref "IC10") (pin "9") (pinfunction "CS_9") (pintype "bidirectional"))
      (node (ref "U$1") (pin "5") (pinfunction "5/PWM_5") (pintype "bidirectional"))
    )
    (net (code "18") (name "ENC_A1") (class "Default")
      (node (ref "C17") (pin "2") (pinfunction "2_2") (pintype "passive"))
      (node (ref "ENC1") (pin "A") (pinfunction "A_A") (pintype "bidirectional"))
      (node (ref "R28") (pin "P$1") (pinfunction "1_P$1") (pintype "passive"))
      (node (ref "U$1") (pin "17/A3") (pinfunction "17/A3/T_17/A3") (pintype "bidirectional"))
    )
    (net (code "19") (name "ENC_A2") (class "Default")
      (node (ref "C19") (pin "2") (pinfunction "2_2") (pintype "passive"))
      (node (ref "ENC2") (pin "A") (pinfunction "A_A") (pintype "bidirectional"))
      (node (ref "R33") (pin "P$1") (pinfunction "1_P$1") (pintype "passive"))
      (node (ref "U$1") (pin "14/A0") (pinfunction "14/A0_14/A0") (pintype "bidirectional"))
    )
    (net (code "20") (name "ENC_B1") (class "Default")
      (node (ref "C16") (pin "2") (pinfunction "2_2") (pintype "passive"))
      (node (ref "ENC1") (pin "B") (pinfunction "B_B") (pintype "bidirectional"))
      (node (ref "R19") (pin "1") (pinfunction "P$1_1") (pintype "passive"))
      (node (ref "U$1") (pin "7") (pinfunction "7/RX3_7") (pintype "bidirectional"))
    )
    (net (code "21") (name "ENC_B2") (class "Default")
      (node (ref "C18") (pin "2") (pinfunction "2_2") (pintype "passive"))
      (node (ref "ENC2") (pin "B") (pinfunction "B_B") (pintype "bidirectional"))
      (node (ref "R32") (pin "1") (pinfunction "P$1_1") (pintype "passive"))
      (node (ref "U$1") (pin "16/A2") (pinfunction "16/A2/T_16/A2") (pintype "bidirectional"))
    )
    (net (code "22") (name "ENC_SW1") (class "Default")
      (node (ref "ENC1") (pin "E") (pinfunction "E_E") (pintype "bidirectional"))
      (node (ref "R29") (pin "1") (pinfunction "P$1_1") (pintype "passive"))
      (node (ref "U$1") (pin "8") (pinfunction "8/TX3_8") (pintype "bidirectional"))
    )
    (net (code "23") (name "ENC_SW2") (class "Default")
      (node (ref "ENC2") (pin "E") (pinfunction "E_E") (pintype "bidirectional"))
      (node (ref "R34") (pin "1") (pinfunction "P$1_1") (pintype "passive"))
      (node (ref "U$1") (pin "15/A1") (pinfunction "15/A1/T_15/A1") (pintype "bidirectional"))
    )
    (net (code "24") (name "GND") (class "Default")
      (node (ref "C1") (pin "1") (pinfunction "P$1_1") (pintype "passive"))
      (node (ref "C16") (pin "1") (pinfunction "1_1") (pintype "passive"))
      (node (ref "C17") (pin "1") (pinfunction "1_1") (pintype "passive"))
      (node (ref "C18") (pin "1") (pinfunction "1_1") (pintype "passive"))
      (node (ref "C19") (pin "1") (pinfunction "1_1") (pintype "passive"))
      (node (ref "C2") (pin "1") (pinfunction "P$1_1") (pintype "passive"))
      (node (ref "IC10") (pin "12") (pinfunction "VSS_12") (pintype "power_in"))
      (node (ref "IC4") (pin "12") (pinfunction "VSS_12") (pintype "power_in"))
      (node (ref "IC5") (pin "12") (pinfunction "VSS_12") (pintype "power_in"))
      (node (ref "IC8") (pin "12") (pinfunction "VSS_12") (pintype "power_in"))
      (node (ref "L3") (pin "2") (pinfunction "P$2_2") (pintype "passive"))
      (node (ref "LCD_HEADER") (pin "2") (pinfunction "2_2") (pintype "passive"))
      (node (ref "LCD_HEADER") (pin "4") (pinfunction "4_4") (pintype "passive"))
      (node (ref "R30") (pin "1") (pinfunction "P$1_1") (pintype "passive"))
      (node (ref "R31") (pin "1") (pinfunction "P$1_1") (pintype "passive"))
      (node (ref "R35") (pin "1") (pinfunction "P$1_1") (pintype "passive"))
      (node (ref "R36") (pin "1") (pinfunction "P$1_1") (pintype "passive"))
      (node (ref "U$1") (pin "GND") (pinfunction "GND_GND") (pintype "power_in"))
      (node (ref "U$1") (pin "GND1") (pinfunction "GND_GND1") (pintype "power_in"))
    )
    (net (code "25") (name "I1") (class "Default")
      (node (ref "IC4") (pin "16") (pinfunction "A2_16") (pintype "bidirectional"))
      (node (ref "JP1") (pin "5") (pinfunction "5_5") (pintype "passive"))
      (node (ref "TP6") (pin "P$1") (pinfunction "P$1_P$1") (pintype "bidirectional"))
    )
    (net (code "26") (name "I2") (class "Default")
      (node (ref "IC5") (pin "16") (pinfunction "A2_16") (pintype "bidirectional"))
      (node (ref "JP2") (pin "5") (pinfunction "5_5") (pintype "passive"))
      (node (ref "TP13") (pin "P$1") (pinfunction "P$1_P$1") (pintype "bidirectional"))
    )
    (net (code "27") (name "I3") (class "Default")
      (node (ref "IC8") (pin "16") (pinfunction "A2_16") (pintype "bidirectional"))
      (node (ref "JP8") (pin "5") (pinfunction "5_5") (pintype "passive"))
      (node (ref "TP19") (pin "P$1") (pinfunction "P$1_P$1") (pintype "bidirectional"))
    )
    (net (code "28") (name "I4") (class "Default")
      (node (ref "IC10") (pin "16") (pinfunction "A2_16") (pintype "bidirectional"))
      (node (ref "JP11") (pin "5") (pinfunction "5_5") (pintype "passive"))
      (node (ref "TP25") (pin "P$1") (pinfunction "P$1_P$1") (pintype "bidirectional"))
    )
    (net (code "29") (name "LIMA1") (class "Default")
      (node (ref "JP1") (pin "4") (pinfunction "4_4") (pintype "passive"))
      (node (ref "R2") (pin "2") (pinfunction "P$2_2") (pintype "passive"))
      (node (ref "T1") (pin "3") (pinfunction "C_3") (pintype "passive"))
    )
    (net (code "30") (name "LIMA2") (class "Default")
      (node (ref "JP2") (pin "4") (pinfunction "4_4") (pintype "passive"))
      (node (ref "R38") (pin "2") (pinfunction "P$2_2") (pintype "passive"))
      (node (ref "T3") (pin "3") (pinfunction "C_3") (pintype "passive"))
    )
    (net (code "31") (name "LIMA3") (class "Default")
      (node (ref "JP8") (pin "4") (pinfunction "4_4") (pintype "passive"))
      (node (ref "R56") (pin "2") (pinfunction "P$2_2") (pintype "passive"))
      (node (ref "T5") (pin "3") (pinfunction "C_3") (pintype "passive"))
    )
    (net (code "32") (name "LIMA4") (class "Default")
      (node (ref "JP11") (pin "4") (pinfunction "4_4") (pintype "passive"))
      (node (ref "R74") (pin "2") (pinfunction "P$2_2") (pintype "passive"))
      (node (ref "T7") (pin "3") (pinfunction "C_3") (pintype "passive"))
    )
    (net (code "33") (name "LIMB1") (class "Default")
      (node (ref "JP1") (pin "6") (pinfunction "6_6") (pintype "passive"))
      (node (ref "R4") (pin "2") (pinfunction "P$2_2") (pintype "passive"))
      (node (ref "T2") (pin "3") (pinfunction "C_3") (pintype "passive"))
    )
    (net (code "34") (name "LIMB2") (class "Default")
      (node (ref "JP2") (pin "6") (pinfunction "6_6") (pintype "passive"))
      (node (ref "R40") (pin "2") (pinfunction "P$2_2") (pintype "passive"))
      (node (ref "T4") (pin "3") (pinfunction "C_3") (pintype "passive"))
    )
    (net (code "35") (name "LIMB3") (class "Default")
      (node (ref "JP8") (pin "6") (pinfunction "6_6") (pintype "passive"))
      (node (ref "R58") (pin "2") (pinfunction "P$2_2") (pintype "passive"))
      (node (ref "T6") (pin "3") (pinfunction "C_3") (pintype "passive"))
    )
    (net (code "36") (name "LIMB4") (class "Default")
      (node (ref "JP11") (pin "6") (pinfunction "6_6") (pintype "passive"))
      (node (ref "R76") (pin "2") (pinfunction "P$2_2") (pintype "passive"))
      (node (ref "T8") (pin "3") (pinfunction "C_3") (pintype "passive"))
    )
    (net (code "37") (name "MOSI") (class "Default")
      (node (ref "LCD_HEADER") (pin "3") (pinfunction "3_3") (pintype "passive"))
      (node (ref "U$1") (pin "11") (pinfunction "11/MOSI_11") (pintype "bidirectional"))
    )
    (net (code "38") (name "MOSI_B") (class "Default")
      (node (ref "IC10") (pin "8") (pinfunction "SDI_8") (pintype "bidirectional"))
      (node (ref "IC3") (pin "8") (pinfunction "DIN_8") (pintype "bidirectional"))
      (node (ref "IC4") (pin "8") (pinfunction "SDI_8") (pintype "bidirectional"))
      (node (ref "IC5") (pin "8") (pinfunction "SDI_8") (pintype "bidirectional"))
      (node (ref "IC8") (pin "8") (pinfunction "SDI_8") (pintype "bidirectional"))
      (node (ref "U$1") (pin "0") (pinfunction "0/RX1/T_0") (pintype "bidirectional"))
    )
    (net (code "39") (name "Net-(C1-P$2)") (class "Default")
      (node (ref "C1") (pin "2") (pinfunction "P$2_2") (pintype "passive"))
      (node (ref "C2") (pin "2") (pinfunction "P$2_2") (pintype "passive"))
      (node (ref "L2") (pin "1") (pinfunction "P$1_1") (pintype "passive"))
      (node (ref "U$1") (pin "VIN") (pinfunction "VIN_VIN") (pintype "power_in"))
    )
    (net (code "40") (name "Net-(C26-P$1)") (class "Default")
      (node (ref "C26") (pin "1") (pinfunction "P$1_1") (pintype "passive"))
      (node (ref "JP14") (pin "1") (pinfunction "1_1") (pintype "passive"))
    )
    (net (code "41") (name "Net-(C27-P$2)") (class "Default")
      (node (ref "C27") (pin "2") (pinfunction "P$2_2") (pintype "passive"))
      (node (ref "C30") (pin "2") (pinfunction "P$2_2") (pintype "passive"))
      (node (ref "IC3") (pin "9") (pinfunction "VDD_9") (pintype "power_in"))
      (node (ref "L1") (pin "1") (pinfunction "P$1_1") (pintype "passive"))
    )
    (net (code "42") (name "Net-(ENC1-GND)") (class "Default")
      (node (ref "ENC1") (pin "C") (pinfunction "GND_C") (pintype "bidirectional"))
      (node (ref "R30") (pin "2") (pinfunction "P$2_2") (pintype "passive"))
    )
    (net (code "43") (name "Net-(ENC2-GND)") (class "Default")
      (node (ref "ENC2") (pin "C") (pinfunction "GND_C") (pintype "bidirectional"))
      (node (ref "R35") (pin "2") (pinfunction "P$2_2") (pintype "passive"))
    )
    (net (code "44") (name "Net-(IC1A--IN)") (class "Default")
      (node (ref "IC1") (pin "2") (pinfunction "-IN_2") (pintype "input"))
      (node (ref "R6") (pin "P$1") (pinfunction "1_P$1") (pintype "passive"))
      (node (ref "R8") (pin "1") (pinfunction "P$1_1") (pintype "passive"))
      (node (ref "TP2") (pin "P$1") (pinfunction "P$1_P$1") (pintype "bidirectional"))
    )
    (net (code "45") (name "Net-(IC1A-OUT)") (class "Default")
      (node (ref "IC1") (pin "1") (pinfunction "OUT_1") (pintype "output"))
      (node (ref "R10") (pin "2") (pinfunction "P$2_2") (pintype "passive"))
      (node (ref "R9") (pin "1") (pinfunction "P$1_1") (pintype "passive"))
    )
    (net (code "46") (name "Net-(IC1B-+IN)") (class "Default")
      (node (ref "IC1") (pin "5") (pinfunction "+IN_5") (pintype "input"))
      (node (ref "R11") (pin "1") (pinfunction "P$1_1") (pintype "passive"))
      (node (ref "R7") (pin "P$1") (pinfunction "1_P$1") (pintype "passive"))
      (node (ref "TP3") (pin "P$1") (pinfunction "P$1_P$1") (pintype "bidirectional"))
    )
    (net (code "47") (name "Net-(IC1B-OUT)") (class "Default")
      (node (ref "IC1") (pin "7") (pinfunction "OUT_7") (pintype "output"))
      (node (ref "R12") (pin "1") (pinfunction "P$1_1") (pintype "passive"))
      (node (ref "R13") (pin "2") (pinfunction "P$2_2") (pintype "passive"))
    )
    (net (code "48") (name "Net-(IC2A--IN)") (class "Default")
      (node (ref "IC2") (pin "2") (pinfunction "-IN_2") (pintype "input"))
      (node (ref "R41") (pin "P$1") (pinfunction "1_P$1") (pintype "passive"))
      (node (ref "R43") (pin "1") (pinfunction "P$1_1") (pintype "passive"))
      (node (ref "TP9") (pin "P$1") (pinfunction "P$1_P$1") (pintype "bidirectional"))
    )
    (net (code "49") (name "Net-(IC2A-OUT)") (class "Default")
      (node (ref "IC2") (pin "1") (pinfunction "OUT_1") (pintype "output"))
      (node (ref "R44") (pin "1") (pinfunction "P$1_1") (pintype "passive"))
      (node (ref "R45") (pin "2") (pinfunction "P$2_2") (pintype "passive"))
    )
    (net (code "50") (name "Net-(IC2B-+IN)") (class "Default")
      (node (ref "IC2") (pin "5") (pinfunction "+IN_5") (pintype "input"))
      (node (ref "R42") (pin "P$1") (pinfunction "1_P$1") (pintype "passive"))
      (node (ref "R46") (pin "1") (pinfunction "P$1_1") (pintype "passive"))
      (node (ref "TP10") (pin "P$1") (pinfunction "P$1_P$1") (pintype "bidirectional"))
    )
    (net (code "51") (name "Net-(IC2B-OUT)") (class "Default")
      (node (ref "IC2") (pin "7") (pinfunction "OUT_7") (pintype "output"))
      (node (ref "R47") (pin "1") (pinfunction "P$1_1") (pintype "passive"))
      (node (ref "R48") (pin "2") (pinfunction "P$2_2") (pintype "passive"))
    )
    (net (code "52") (name "Net-(IC3-VREF)") (class "Default")
      (node (ref "IC3") (pin "10") (pinfunction "VREF_10") (pintype "bidirectional"))
      (node (ref "JP14") (pin "3") (pinfunction "3_3") (pintype "passive"))
      (node (ref "JP14") (pin "4") (pinfunction "4_4") (pintype "passive"))
      (node (ref "TP1") (pin "P$1") (pinfunction "P$1_P$1") (pintype "bidirectional"))
    )
    (net (code "53") (name "Net-(IC7A--IN)") (class "Default")
      (node (ref "IC7") (pin "2") (pinfunction "-IN_2") (pintype "input"))
      (node (ref "R59") (pin "P$1") (pinfunction "1_P$1") (pintype "passive"))
      (node (ref "R61") (pin "1") (pinfunction "P$1_1") (pintype "passive"))
      (node (ref "TP15") (pin "P$1") (pinfunction "P$1_P$1") (pintype "bidirectional"))
    )
    (net (code "54") (name "Net-(IC7A-OUT)") (class "Default")
      (node (ref "IC7") (pin "1") (pinfunction "OUT_1") (pintype "output"))
      (node (ref "R62") (pin "1") (pinfunction "P$1_1") (pintype "passive"))
      (node (ref "R63") (pin "2") (pinfunction "P$2_2") (pintype "passive"))
    )
    (net (code "55") (name "Net-(IC7B-+IN)") (class "Default")
      (node (ref "IC7") (pin "5") (pinfunction "+IN_5") (pintype "input"))
      (node (ref "R60") (pin "P$1") (pinfunction "1_P$1") (pintype "passive"))
      (node (ref "R64") (pin "1") (pinfunction "P$1_1") (pintype "passive"))
      (node (ref "TP16") (pin "P$1") (pinfunction "P$1_P$1") (pintype "bidirectional"))
    )
    (net (code "56") (name "Net-(IC7B-OUT)") (class "Default")
      (node (ref "IC7") (pin "7") (pinfunction "OUT_7") (pintype "output"))
      (node (ref "R65") (pin "1") (pinfunction "P$1_1") (pintype "passive"))
      (node (ref "R66") (pin "2") (pinfunction "P$2_2") (pintype "passive"))
    )
    (net (code "57") (name "Net-(IC9A--IN)") (class "Default")
      (node (ref "IC9") (pin "2") (pinfunction "-IN_2") (pintype "input"))
      (node (ref "R77") (pin "P$1") (pinfunction "1_P$1") (pintype "passive"))
      (node (ref "R79") (pin "1") (pinfunction "P$1_1") (pintype "passive"))
      (node (ref "TP21") (pin "P$1") (pinfunction "P$1_P$1") (pintype "bidirectional"))
    )
    (net (code "58") (name "Net-(IC9A-OUT)") (class "Default")
      (node (ref "IC9") (pin "1") (pinfunction "OUT_1") (pintype "output"))
      (node (ref "R80") (pin "1") (pinfunction "P$1_1") (pintype "passive"))
      (node (ref "R81") (pin "2") (pinfunction "P$2_2") (pintype "passive"))
    )
    (net (code "59") (name "Net-(IC9B-+IN)") (class "Default")
      (node (ref "IC9") (pin "5") (pinfunction "+IN_5") (pintype "input"))
      (node (ref "R78") (pin "P$1") (pinfunction "1_P$1") (pintype "passive"))
      (node (ref "R82") (pin "1") (pinfunction "P$1_1") (pintype "passive"))
      (node (ref "TP22") (pin "P$1") (pinfunction "P$1_P$1") (pintype "bidirectional"))
    )
    (net (code "60") (name "Net-(IC9B-OUT)") (class "Default")
      (node (ref "IC9") (pin "7") (pinfunction "OUT_7") (pintype "output"))
      (node (ref "R83") (pin "1") (pinfunction "P$1_1") (pintype "passive"))
      (node (ref "R84") (pin "2") (pinfunction "P$2_2") (pintype "passive"))
    )
    (net (code "61") (name "Net-(LCD_HEADER-Pad1)") (class "Default")
      (node (ref "LCD_HEADER") (pin "1") (pinfunction "1_1") (pintype "passive"))
      (node (ref "U$1") (pin "3.3V") (pinfunction "3.3V_3.3V") (pintype "power_in"))
      (node (ref "U$1") (pin "3.3V1") (pinfunction "3.3V_3.3V1") (pintype "power_in"))
    )
    (net (code "62") (name "Net-(R1-P$2)") (class "Default")
      (node (ref "JP3") (pin "1") (pinfunction "1_1") (pintype "passive"))
      (node (ref "R1") (pin "2") (pinfunction "P$2_2") (pintype "passive"))
      (node (ref "R2") (pin "1") (pinfunction "P$1_1") (pintype "passive"))
      (node (ref "S1") (pin "P$3") (pinfunction "3_P$3") (pintype "bidirectional"))
    )
    (net (code "63") (name "Net-(R3-P$2)") (class "Default")
      (node (ref "JP5") (pin "1") (pinfunction "1_1") (pintype "passive"))
      (node (ref "R3") (pin "2") (pinfunction "P$2_2") (pintype "passive"))
      (node (ref "R4") (pin "1") (pinfunction "P$1_1") (pintype "passive"))
      (node (ref "S1") (pin "P$6") (pinfunction "6_P$6") (pintype "bidirectional"))
    )
    (net (code "64") (name "Net-(R5-P$1)") (class "Default")
      (node (ref "R5") (pin "1") (pinfunction "P$1_1") (pintype "passive"))
      (node (ref "S1") (pin "P$4") (pinfunction "4_P$4") (pintype "bidirectional"))
    )
    (net (code "65") (name "Net-(R5-P$2)") (class "Default")
      (node (ref "D1") (pin "C") (pinfunction "C_C") (pintype "bidirectional"))
      (node (ref "R5") (pin "2") (pinfunction "P$2_2") (pintype "passive"))
    )
    (net (code "66") (name "Net-(R10-P$1)") (class "Default")
      (node (ref "R10") (pin "1") (pinfunction "P$1_1") (pintype "passive"))
      (node (ref "T1") (pin "1") (pinfunction "B_1") (pintype "passive"))
    )
    (net (code "67") (name "Net-(R13-P$1)") (class "Default")
      (node (ref "R13") (pin "1") (pinfunction "P$1_1") (pintype "passive"))
      (node (ref "T2") (pin "1") (pinfunction "B_1") (pintype "passive"))
    )
    (net (code "68") (name "Net-(R14-P$1)") (class "Default")
      (node (ref "JP1") (pin "8") (pinfunction "8_8") (pintype "passive"))
      (node (ref "R14") (pin "1") (pinfunction "P$1_1") (pintype "passive"))
      (node (ref "R15") (pin "1") (pinfunction "P$1_1") (pintype "passive"))
    )
    (net (code "69") (name "Net-(R14-P$2)") (class "Default")
      (node (ref "R14") (pin "2") (pinfunction "P$2_2") (pintype "passive"))
      (node (ref "X1") (pin "1") (pinfunction "1_1") (pintype "passive"))
    )
    (net (code "70") (name "Net-(R18-P$2)") (class "Default")
      (node (ref "R18") (pin "2") (pinfunction "P$2_2") (pintype "passive"))
      (node (ref "X2") (pin "1") (pinfunction "1_1") (pintype "passive"))
    )
    (net (code "71") (name "Net-(R31-P$2)") (class "Default")
      (node (ref "ENC1") (pin "D") (pinfunction "D_D") (pintype "bidirectional"))
      (node (ref "R31") (pin "2") (pinfunction "P$2_2") (pintype "passive"))
    )
    (net (code "72") (name "Net-(R36-P$2)") (class "Default")
      (node (ref "ENC2") (pin "D") (pinfunction "D_D") (pintype "bidirectional"))
      (node (ref "R36") (pin "2") (pinfunction "P$2_2") (pintype "passive"))
    )
    (net (code "73") (name "Net-(R37-P$2)") (class "Default")
      (node (ref "JP6") (pin "1") (pinfunction "1_1") (pintype "passive"))
      (node (ref "R37") (pin "2") (pinfunction "P$2_2") (pintype "passive"))
      (node (ref "R38") (pin "1") (pinfunction "P$1_1") (pintype "passive"))
      (node (ref "S2") (pin "P$3") (pinfunction "3_P$3") (pintype "bidirectional"))
    )
    (net (code "74") (name "Net-(R39-P$2)") (class "Default")
      (node (ref "JP7") (pin "1") (pinfunction "1_1") (pintype "passive"))
      (node (ref "R39") (pin "2") (pinfunction "P$2_2") (pintype "passive"))
      (node (ref "R40") (pin "1") (pinfunction "P$1_1") (pintype "passive"))
      (node (ref "S2") (pin "P$6") (pinfunction "6_P$6") (pintype "bidirectional"))
    )
    (net (code "75") (name "Net-(R45-P$1)") (class "Default")
      (node (ref "R45") (pin "1") (pinfunction "P$1_1") (pintype "passive"))
      (node (ref "T3") (pin "1") (pinfunction "B_1") (pintype "passive"))
    )
    (net (code "76") (name "Net-(R48-P$1)") (class "Default")
      (node (ref "R48") (pin "1") (pinfunction "P$1_1") (pintype "passive"))
      (node (ref "T4") (pin "1") (pinfunction "B_1") (pintype "passive"))
    )
    (net (code "77") (name "Net-(R49-P$1)") (class "Default")
      (node (ref "R49") (pin "1") (pinfunction "P$1_1") (pintype "passive"))
      (node (ref "S2") (pin "P$4") (pinfunction "4_P$4") (pintype "bidirectional"))
    )
    (net (code "78") (name "Net-(R49-P$2)") (class "Default")
      (node (ref "D2") (pin "C") (pinfunction "C_C") (pintype "bidirectional"))
      (node (ref "R49") (pin "2") (pinfunction "P$2_2") (pintype "passive"))
    )
    (net (code "79") (name "Net-(R52-P$1)") (class "Default")
      (node (ref "JP2") (pin "8") (pinfunction "8_8") (pintype "passive"))
      (node (ref "R52") (pin "1") (pinfunction "P$1_1") (pintype "passive"))
      (node (ref "R53") (pin "1") (pinfunction "P$1_1") (pintype "passive"))
    )
    (net (code "80") (name "Net-(R52-P$2)") (class "Default")
      (node (ref "R52") (pin "2") (pinfunction "P$2_2") (pintype "passive"))
      (node (ref "X3") (pin "1") (pinfunction "1_1") (pintype "passive"))
    )
    (net (code "81") (name "Net-(R54-P$2)") (class "Default")
      (node (ref "R54") (pin "2") (pinfunction "P$2_2") (pintype "passive"))
      (node (ref "X4") (pin "1") (pinfunction "1_1") (pintype "passive"))
    )
    (net (code "82") (name "Net-(R55-P$2)") (class "Default")
      (node (ref "JP9") (pin "1") (pinfunction "1_1") (pintype "passive"))
      (node (ref "R55") (pin "2") (pinfunction "P$2_2") (pintype "passive"))
      (node (ref "R56") (pin "1") (pinfunction "P$1_1") (pintype "passive"))
      (node (ref "S3") (pin "P$3") (pinfunction "3_P$3") (pintype "bidirectional"))
    )
    (net (code "83") (name "Net-(R57-P$2)") (class "Default")
      (node (ref "JP10") (pin "1") (pinfunction "1_1") (pintype "passive"))
      (node (ref "R57") (pin "2") (pinfunction "P$2_2") (pintype "passive"))
      (node (ref "R58") (pin "1") (pinfunction "P$1_1") (pintype "passive"))
      (node (ref "S3") (pin "P$6") (pinfunction "6_P$6") (pintype "bidirectional"))
    )
    (net (code "84") (name "Net-(R63-P$1)") (class "Default")
      (node (ref "R63") (pin "1") (pinfunction "P$1_1") (pintype "passive"))
      (node (ref "T5") (pin "1") (pinfunction "B_1") (pintype "passive"))
    )
    (net (code "85") (name "Net-(R66-P$1)") (class "Default")
      (node (ref "R66") (pin "1") (pinfunction "P$1_1") (pintype "passive"))
      (node (ref "T6") (pin "1") (pinfunction "B_1") (pintype "passive"))
    )
    (net (code "86") (name "Net-(R67-P$1)") (class "Default")
      (node (ref "R67") (pin "1") (pinfunction "P$1_1") (pintype "passive"))
      (node (ref "S3") (pin "P$4") (pinfunction "4_P$4") (pintype "bidirectional"))
    )
    (net (code "87") (name "Net-(R67-P$2)") (class "Default")
      (node (ref "D3") (pin "C") (pinfunction "C_C") (pintype "bidirectional"))
      (node (ref "R67") (pin "2") (pinfunction "P$2_2") (pintype "passive"))
    )
    (net (code "88") (name "Net-(R70-P$1)") (class "Default")
      (node (ref "JP8") (pin "8") (pinfunction "8_8") (pintype "passive"))
      (node (ref "R70") (pin "1") (pinfunction "P$1_1") (pintype "passive"))
      (node (ref "R71") (pin "1") (pinfunction "P$1_1") (pintype "passive"))
    )
    (net (code "89") (name "Net-(R70-P$2)") (class "Default")
      (node (ref "R70") (pin "2") (pinfunction "P$2_2") (pintype "passive"))
      (node (ref "X5") (pin "1") (pinfunction "1_1") (pintype "passive"))
    )
    (net (code "90") (name "Net-(R72-P$2)") (class "Default")
      (node (ref "R72") (pin "2") (pinfunction "P$2_2") (pintype "passive"))
      (node (ref "X6") (pin "1") (pinfunction "1_1") (pintype "passive"))
    )
    (net (code "91") (name "Net-(R73-P$2)") (class "Default")
      (node (ref "JP12") (pin "1") (pinfunction "1_1") (pintype "passive"))
      (node (ref "R73") (pin "2") (pinfunction "P$2_2") (pintype "passive"))
      (node (ref "R74") (pin "1") (pinfunction "P$1_1") (pintype "passive"))
      (node (ref "S4") (pin "P$3") (pinfunction "3_P$3") (pintype "bidirectional"))
    )
    (net (code "92") (name "Net-(R75-P$2)") (class "Default")
      (node (ref "JP13") (pin "1") (pinfunction "1_1") (pintype "passive"))
      (node (ref "R75") (pin "2") (pinfunction "P$2_2") (pintype "passive"))
      (node (ref "R76") (pin "1") (pinfunction "P$1_1") (pintype "passive"))
      (node (ref "S4") (pin "P$6") (pinfunction "6_P$6") (pintype "bidirectional"))
    )
    (net (code "93") (name "Net-(R81-P$1)") (class "Default")
      (node (ref "R81") (pin "1") (pinfunction "P$1_1") (pintype "passive"))
      (node (ref "T7") (pin "1") (pinfunction "B_1") (pintype "passive"))
    )
    (net (code "94") (name "Net-(R84-P$1)") (class "Default")
      (node (ref "R84") (pin "1") (pinfunction "P$1_1") (pintype "passive"))
      (node (ref "T8") (pin "1") (pinfunction "B_1") (pintype "passive"))
    )
    (net (code "95") (name "Net-(R85-P$1)") (class "Default")
      (node (ref "R85") (pin "1") (pinfunction "P$1_1") (pintype "passive"))
      (node (ref "S4") (pin "P$4") (pinfunction "4_P$4") (pintype "bidirectional"))
    )
    (net (code "96") (name "Net-(R85-P$2)") (class "Default")
      (node (ref "D4") (pin "C") (pinfunction "C_C") (pintype "bidirectional"))
      (node (ref "R85") (pin "2") (pinfunction "P$2_2") (pintype "passive"))
    )
    (net (code "97") (name "Net-(R88-P$1)") (class "Default")
      (node (ref "JP11") (pin "8") (pinfunction "8_8") (pintype "passive"))
      (node (ref "R88") (pin "1") (pinfunction "P$1_1") (pintype "passive"))
      (node (ref "R89") (pin "1") (pinfunction "P$1_1") (pintype "passive"))
    )
    (net (code "98") (name "Net-(R88-P$2)") (class "Default")
      (node (ref "R88") (pin "2") (pinfunction "P$2_2") (pintype "passive"))
      (node (ref "X7") (pin "1") (pinfunction "1_1") (pintype "passive"))
    )
    (net (code "99") (name "Net-(R90-P$2)") (class "Default")
      (node (ref "R90") (pin "2") (pinfunction "P$2_2") (pintype "passive"))
      (node (ref "X8") (pin "1") (pinfunction "1_1") (pintype "passive"))
    )
    (net (code "100") (name "P1") (class "Default")
      (node (ref "IC4") (pin "2") (pinfunction "A1_2") (pintype "bidirectional"))
      (node (ref "JP1") (pin "1") (pinfunction "1_1") (pintype "passive"))
      (node (ref "TP4") (pin "P$1") (pinfunction "P$1_P$1") (pintype "bidirectional"))
    )
    (net (code "101") (name "P2") (class "Default")
      (node (ref "IC5") (pin "2") (pinfunction "A1_2") (pintype "bidirectional"))
      (node (ref "JP2") (pin "1") (pinfunction "1_1") (pintype "passive"))
      (node (ref "TP11") (pin "P$1") (pinfunction "P$1_P$1") (pintype "bidirectional"))
    )
    (net (code "102") (name "P3") (class "Default")
      (node (ref "IC8") (pin "2") (pinfunction "A1_2") (pintype "bidirectional"))
      (node (ref "JP8") (pin "1") (pinfunction "1_1") (pintype "passive"))
      (node (ref "TP17") (pin "P$1") (pinfunction "P$1_P$1") (pintype "bidirectional"))
    )
    (net (code "103") (name "P4") (class "Default")
      (node (ref "IC10") (pin "2") (pinfunction "A1_2") (pintype "bidirectional"))
      (node (ref "JP11") (pin "1") (pinfunction "1_1") (pintype "passive"))
      (node (ref "TP23") (pin "P$1") (pinfunction "P$1_P$1") (pintype "bidirectional"))
    )
    (net (code "104") (name "RST_LCD") (class "Default")
      (node (ref "LCD_HEADER") (pin "8") (pinfunction "8_8") (pintype "passive"))
      (node (ref "U$1") (pin "9") (pinfunction "9/RX2/PWM_9") (pintype "bidirectional"))
    )
    (net (code "105") (name "RS_LCD") (class "Default")
      (node (ref "LCD_HEADER") (pin "7") (pinfunction "7_7") (pintype "passive"))
      (node (ref "U$1") (pin "10") (pinfunction "10/TX2/PWM_10") (pintype "bidirectional"))
    )
    (net (code "106") (name "SCK") (class "Default")
      (node (ref "LCD_HEADER") (pin "5") (pinfunction "5_5") (pintype "passive"))
      (node (ref "U$1") (pin "13") (pinfunction "13/SCK/LED_13") (pintype "bidirectional"))
    )
    (net (code "107") (name "SCK_B") (class "Default")
      (node (ref "IC10") (pin "7") (pinfunction "CLK_7") (pintype "bidirectional"))
      (node (ref "IC3") (pin "7") (pinfunction "SCLK_7") (pintype "bidirectional"))
      (node (ref "IC4") (pin "7") (pinfunction "CLK_7") (pintype "bidirectional"))
      (node (ref "IC5") (pin "7") (pinfunction "CLK_7") (pintype "bidirectional"))
      (node (ref "IC8") (pin "7") (pinfunction "CLK_7") (pintype "bidirectional"))
      (node (ref "U$1") (pin "1") (pinfunction "1/TX1/T_1") (pintype "bidirectional"))
    )
    (net (code "108") (name "VBAT") (class "Default")
      (node (ref "U$1") (pin "VBAT") (pinfunction "VBAT_VBAT") (pintype "power_in"))
    )
    (net (code "109") (name "VDD") (class "Default")
      (node (ref "C12") (pin "2") (pinfunction "P$2_2") (pintype "passive"))
      (node (ref "C13") (pin "2") (pinfunction "P$2_2") (pintype "passive"))
      (node (ref "C15") (pin "2") (pinfunction "P$2_2") (pintype "passive"))
      (node (ref "C20") (pin "2") (pinfunction "P$2_2") (pintype "passive"))
      (node (ref "C21") (pin "2") (pinfunction "P$2_2") (pintype "passive"))
      (node (ref "C22") (pin "2") (pinfunction "P$2_2") (pintype "passive"))
      (node (ref "C23") (pin "2") (pinfunction "P$2_2") (pintype "passive"))
      (node (ref "C24") (pin "2") (pinfunction "P$2_2") (pintype "passive"))
      (node (ref "C25") (pin "2") (pinfunction "P$2_2") (pintype "passive"))
      (node (ref "CP3") (pin "+") (pinfunction "+_+") (pintype "passive"))
      (node (ref "D1") (pin "A") (pinfunction "A_A") (pintype "bidirectional"))
      (node (ref "D2") (pin "A") (pinfunction "A_A") (pintype "bidirectional"))
      (node (ref "D3") (pin "A") (pinfunction "A_A") (pintype "bidirectional"))
      (node (ref "D4") (pin "A") (pinfunction "A_A") (pintype "bidirectional"))
      (node (ref "IC1") (pin "8") (pinfunction "V+_8") (pintype "power_in"))
      (node (ref "IC10") (pin "10") (pinfunction "PR_10") (pintype "bidirectional"))
      (node (ref "IC10") (pin "13") (pinfunction "VL_13") (pintype "power_in"))
      (node (ref "IC10") (pin "5") (pinfunction "VDD_5") (pintype "power_in"))
      (node (ref "IC10") (pin "6") (pinfunction "SHDN_6") (pintype "bidirectional"))
      (node (ref "IC2") (pin "8") (pinfunction "V+_8") (pintype "power_in"))
      (node (ref "IC4") (pin "10") (pinfunction "PR_10") (pintype "bidirectional"))
      (node (ref "IC4") (pin "13") (pinfunction "VL_13") (pintype "power_in"))
      (node (ref "IC4") (pin "5") (pinfunction "VDD_5") (pintype "power_in"))
      (node (ref "IC4") (pin "6") (pinfunction "SHDN_6") (pintype "bidirectional"))
      (node (ref "IC5") (pin "10") (pinfunction "PR_10") (pintype "bidirectional"))
      (node (ref "IC5") (pin "13") (pinfunction "VL_13") (pintype "power_in"))
      (node (ref "IC5") (pin "5") (pinfunction "VDD_5") (pintype "power_in"))
      (node (ref "IC5") (pin "6") (pinfunction "SHDN_6") (pintype "bidirectional"))
      (node (ref "IC6") (pin "1") (pinfunction "IN_1") (pintype "bidirectional"))
      (node (ref "IC7") (pin "8") (pinfunction "V+_8") (pintype "power_in"))
      (node (ref "IC8") (pin "10") (pinfunction "PR_10") (pintype "bidirectional"))
      (node (ref "IC8") (pin "13") (pinfunction "VL_13") (pintype "power_in"))
      (node (ref "IC8") (pin "5") (pinfunction "VDD_5") (pintype "power_in"))
      (node (ref "IC8") (pin "6") (pinfunction "SHDN_6") (pintype "bidirectional"))
      (node (ref "IC9") (pin "8") (pinfunction "V+_8") (pintype "power_in"))
      (node (ref "JP1") (pin "11") (pinfunction "11_11") (pintype "passive"))
      (node (ref "JP1") (pin "2") (pinfunction "2_2") (pintype "passive"))
      (node (ref "JP11") (pin "11") (pinfunction "11_11") (pintype "passive"))
      (node (ref "JP11") (pin "2") (pinfunction "2_2") (pintype "passive"))
      (node (ref "JP2") (pin "11") (pinfunction "11_11") (pintype "passive"))
      (node (ref "JP2") (pin "2") (pinfunction "2_2") (pintype "passive"))
      (node (ref "JP8") (pin "11") (pinfunction "11_11") (pintype "passive"))
      (node (ref "JP8") (pin "2") (pinfunction "2_2") (pintype "passive"))
      (node (ref "L1") (pin "2") (pinfunction "P$2_2") (pintype "passive"))
      (node (ref "L2") (pin "2") (pinfunction "P$2_2") (pintype "passive"))
      (node (ref "L4") (pin "1") (pinfunction "P$1_1") (pintype "passive"))
      (node (ref "R11") (pin "2") (pinfunction "P$2_2") (pintype "passive"))
      (node (ref "R12") (pin "2") (pinfunction "P$2_2") (pintype "passive"))
      (node (ref "R19") (pin "2") (pinfunction "P$2_2") (pintype "passive"))
      (node (ref "R28") (pin "P$2") (pinfunction "2_P$2") (pintype "passive"))
      (node (ref "R29") (pin "2") (pinfunction "P$2_2") (pintype "passive"))
      (node (ref "R32") (pin "2") (pinfunction "P$2_2") (pintype "passive"))
      (node (ref "R33") (pin "P$2") (pinfunction "2_P$2") (pintype "passive"))
      (node (ref "R34") (pin "2") (pinfunction "P$2_2") (pintype "passive"))
      (node (ref "R43") (pin "2") (pinfunction "P$2_2") (pintype "passive"))
      (node (ref "R44") (pin "2") (pinfunction "P$2_2") (pintype "passive"))
      (node (ref "R46") (pin "2") (pinfunction "P$2_2") (pintype "passive"))
      (node (ref "R47") (pin "2") (pinfunction "P$2_2") (pintype "passive"))
      (node (ref "R61") (pin "2") (pinfunction "P$2_2") (pintype "passive"))
      (node (ref "R62") (pin "2") (pinfunction "P$2_2") (pintype "passive"))
      (node (ref "R64") (pin "2") (pinfunction "P$2_2") (pintype "passive"))
      (node (ref "R65") (pin "2") (pinfunction "P$2_2") (pintype "passive"))
      (node (ref "R79") (pin "2") (pinfunction "P$2_2") (pintype "passive"))
      (node (ref "R8") (pin "2") (pinfunction "P$2_2") (pintype "passive"))
      (node (ref "R80") (pin "2") (pinfunction "P$2_2") (pintype "passive"))
      (node (ref "R82") (pin "2") (pinfunction "P$2_2") (pintype "passive"))
      (node (ref "R83") (pin "2") (pinfunction "P$2_2") (pintype "passive"))
      (node (ref "R9") (pin "2") (pinfunction "P$2_2") (pintype "passive"))
    )
    (net (code "110") (name "VMON1") (class "Default")
      (node (ref "JP1") (pin "7") (pinfunction "7_7") (pintype "passive"))
      (node (ref "R18") (pin "1") (pinfunction "P$1_1") (pintype "passive"))
      (node (ref "R26") (pin "P$2") (pinfunction "2_P$2") (pintype "passive"))
    )
    (net (code "111") (name "VMON1_B") (class "Default")
      (node (ref "C9") (pin "2") (pinfunction "P$2_2") (pintype "passive"))
      (node (ref "R26") (pin "P$1") (pinfunction "1_P$1") (pintype "passive"))
      (node (ref "R27") (pin "P$2") (pinfunction "2_P$2") (pintype "passive"))
      (node (ref "U$1") (pin "A10") (pinfunction "A10_A10") (pintype "bidirectional"))
    )
    (net (code "112") (name "VMON2") (class "Default")
      (node (ref "JP2") (pin "7") (pinfunction "7_7") (pintype "passive"))
      (node (ref "R24") (pin "P$2") (pinfunction "2_P$2") (pintype "passive"))
      (node (ref "R54") (pin "1") (pinfunction "P$1_1") (pintype "passive"))
    )
    (net (code "113") (name "VMON2_B") (class "Default")
      (node (ref "C6") (pin "2") (pinfunction "P$2_2") (pintype "passive"))
      (node (ref "R24") (pin "P$1") (pinfunction "1_P$1") (pintype "passive"))
      (node (ref "R25") (pin "P$2") (pinfunction "2_P$2") (pintype "passive"))
      (node (ref "U$1") (pin "22/A8") (pinfunction "22/A8/T/PWM_22/A8") (pintype "bidirectional"))
    )
    (net (code "114") (name "VMON3") (class "Default")
      (node (ref "JP8") (pin "7") (pinfunction "7_7") (pintype "passive"))
      (node (ref "R22") (pin "P$2") (pinfunction "2_P$2") (pintype "passive"))
      (node (ref "R72") (pin "1") (pinfunction "P$1_1") (pintype "passive"))
    )
    (net (code "115") (name "VMON3_B") (class "Default")
      (node (ref "C4") (pin "2") (pinfunction "P$2_2") (pintype "passive"))
      (node (ref "R22") (pin "P$1") (pinfunction "1_P$1") (pintype "passive"))
      (node (ref "R23") (pin "P$2") (pinfunction "2_P$2") (pintype "passive"))
      (node (ref "U$1") (pin "20/A6") (pinfunction "20/A6/PWM_20/A6") (pintype "bidirectional"))
    )
    (net (code "116") (name "VMON4") (class "Default")
      (node (ref "JP11") (pin "7") (pinfunction "7_7") (pintype "passive"))
      (node (ref "R20") (pin "P$2") (pinfunction "2_P$2") (pintype "passive"))
      (node (ref "R90") (pin "1") (pinfunction "P$1_1") (pintype "passive"))
    )
    (net (code "117") (name "VMON4_B") (class "Default")
      (node (ref "C3") (pin "2") (pinfunction "P$2_2") (pintype "passive"))
      (node (ref "R20") (pin "P$1") (pinfunction "1_P$1") (pintype "passive"))
      (node (ref "R21") (pin "P$2") (pinfunction "2_P$2") (pintype "passive"))
      (node (ref "U$1") (pin "18/A4") (pinfunction "18/A4/T/SDA0_18/A4") (pintype "bidirectional"))
    )
    (net (code "118") (name "VSET1") (class "Default")
      (node (ref "IC1") (pin "3") (pinfunction "+IN_3") (pintype "input"))
      (node (ref "IC1") (pin "6") (pinfunction "-IN_6") (pintype "input"))
      (node (ref "IC3") (pin "1") (pinfunction "VOUTA_1") (pintype "output"))
      (node (ref "JP1") (pin "10") (pinfunction "10_10") (pintype "passive"))
      (node (ref "TP8") (pin "P$1") (pinfunction "P$1_P$1") (pintype "bidirectional"))
    )
    (net (code "119") (name "VSET2") (class "Default")
      (node (ref "IC2") (pin "3") (pinfunction "+IN_3") (pintype "input"))
      (node (ref "IC2") (pin "6") (pinfunction "-IN_6") (pintype "input"))
      (node (ref "IC3") (pin "2") (pinfunction "VOUTB_2") (pintype "output"))
      (node (ref "JP2") (pin "10") (pinfunction "10_10") (pintype "passive"))
      (node (ref "TP14") (pin "P$1") (pinfunction "P$1_P$1") (pintype "bidirectional"))
    )
    (net (code "120") (name "VSET3") (class "Default")
      (node (ref "IC3") (pin "4") (pinfunction "VOUTC_4") (pintype "output"))
      (node (ref "IC7") (pin "3") (pinfunction "+IN_3") (pintype "input"))
      (node (ref "IC7") (pin "6") (pinfunction "-IN_6") (pintype "input"))
      (node (ref "JP8") (pin "10") (pinfunction "10_10") (pintype "passive"))
      (node (ref "TP20") (pin "P$1") (pinfunction "P$1_P$1") (pintype "bidirectional"))
    )
    (net (code "121") (name "VSET4") (class "Default")
      (node (ref "IC3") (pin "5") (pinfunction "VOUTD_5") (pintype "output"))
      (node (ref "IC9") (pin "3") (pinfunction "+IN_3") (pintype "input"))
      (node (ref "IC9") (pin "6") (pinfunction "-IN_6") (pintype "input"))
      (node (ref "JP11") (pin "10") (pinfunction "10_10") (pintype "passive"))
      (node (ref "TP26") (pin "P$1") (pinfunction "P$1_P$1") (pintype "bidirectional"))
    )
    (net (code "122") (name "VUSB") (class "Default")
      (node (ref "U$1") (pin "VUSB") (pinfunction "VUSB_VUSB") (pintype "power_in"))
    )
    (net (code "123") (name "unconnected-(IC4-SDO-Pad1)") (class "Default")
      (node (ref "IC4") (pin "1") (pinfunction "SDO_1") (pintype "bidirectional"))
    )
    (net (code "124") (name "unconnected-(IC5-SDO-Pad1)") (class "Default")
      (node (ref "IC5") (pin "1") (pinfunction "SDO_1") (pintype "bidirectional"))
    )
    (net (code "125") (name "unconnected-(IC8-SDO-Pad1)") (class "Default")
      (node (ref "IC8") (pin "1") (pinfunction "SDO_1") (pintype "bidirectional"))
    )
    (net (code "126") (name "unconnected-(IC10-SDO-Pad1)") (class "Default")
      (node (ref "IC10") (pin "1") (pinfunction "SDO_1") (pintype "bidirectional"))
    )
    (net (code "127") (name "unconnected-(S1-1-PadP$1)") (class "Default")
      (node (ref "S1") (pin "P$1") (pinfunction "1_P$1") (pintype "bidirectional"))
    )
    (net (code "128") (name "unconnected-(S2-1-PadP$1)") (class "Default")
      (node (ref "S2") (pin "P$1") (pinfunction "1_P$1") (pintype "bidirectional"))
    )
    (net (code "129") (name "unconnected-(S3-1-PadP$1)") (class "Default")
      (node (ref "S3") (pin "P$1") (pinfunction "1_P$1") (pintype "bidirectional"))
    )
    (net (code "130") (name "unconnected-(S4-1-PadP$1)") (class "Default")
      (node (ref "S4") (pin "P$1") (pinfunction "1_P$1") (pintype "bidirectional"))
    )
    (net (code "131") (name "unconnected-(U$1-A14{slash}DAC-PadA14)") (class "Default")
      (node (ref "U$1") (pin "A14") (pinfunction "A14/DAC_A14") (pintype "bidirectional"))
    )
    (net (code "132") (name "unconnected-(U$1-PadPGM)") (class "Default")
      (node (ref "U$1") (pin "PGM") (pinfunction "PGM_PGM") (pintype "bidirectional"))
    )
  )
)
